# Main.net
KiCad netlist of a schematic drawn in Altium Designer
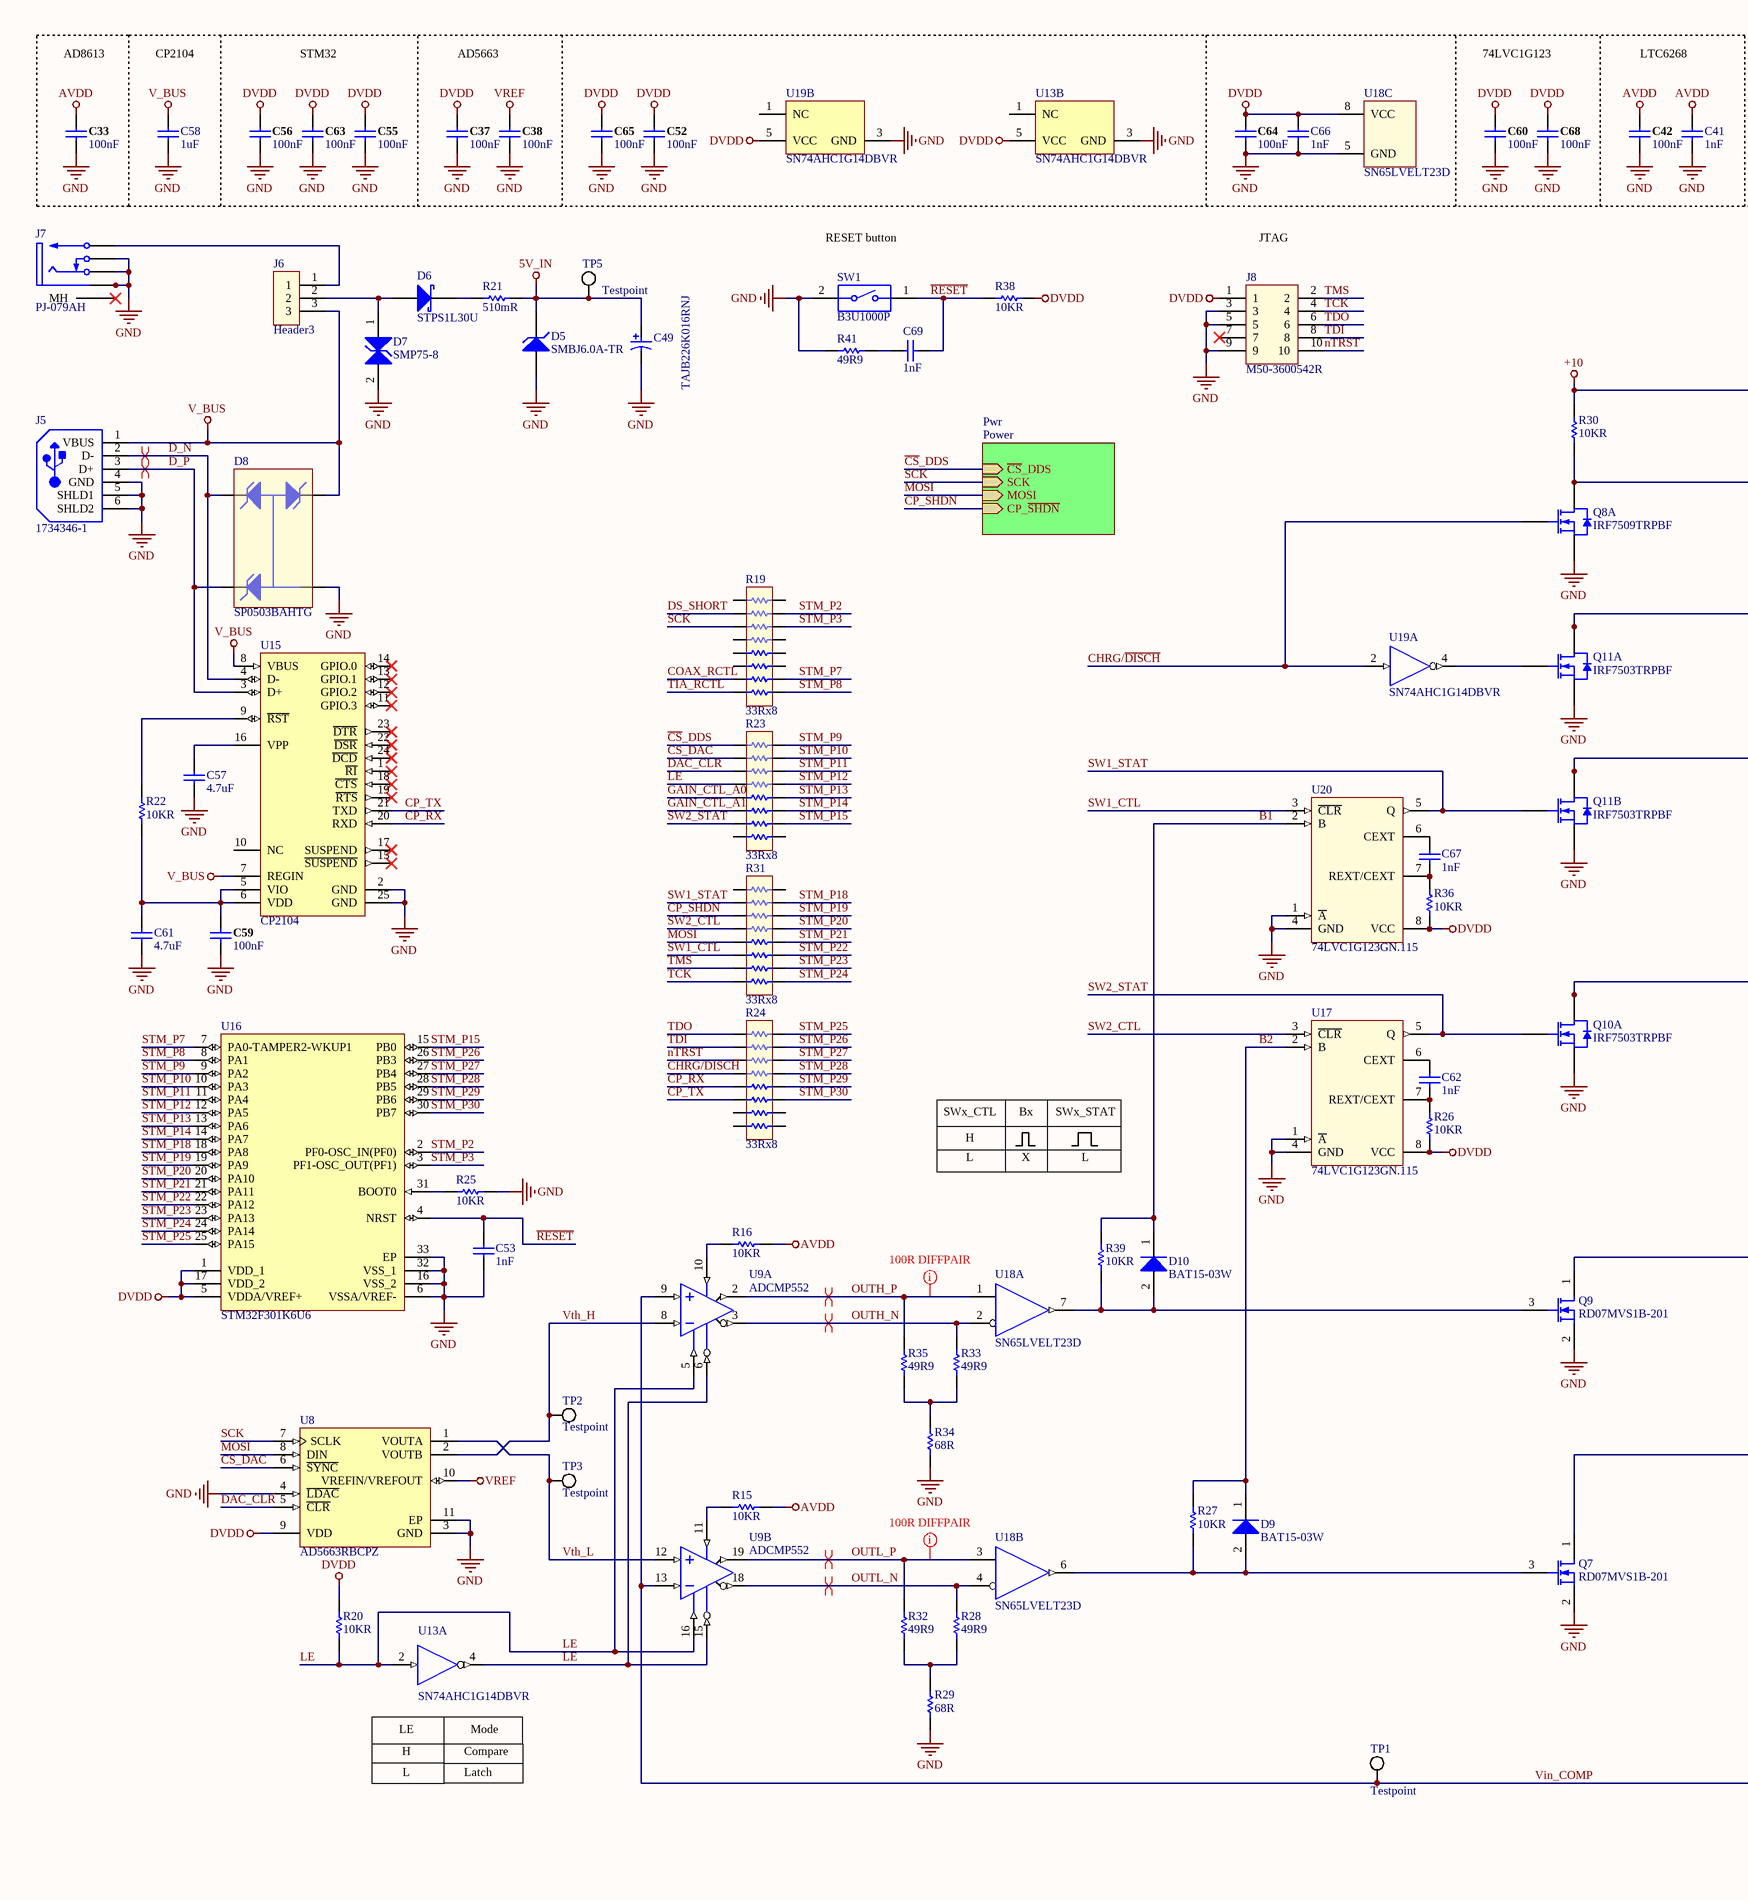
[diagram p0: Main.SchDoc, left]
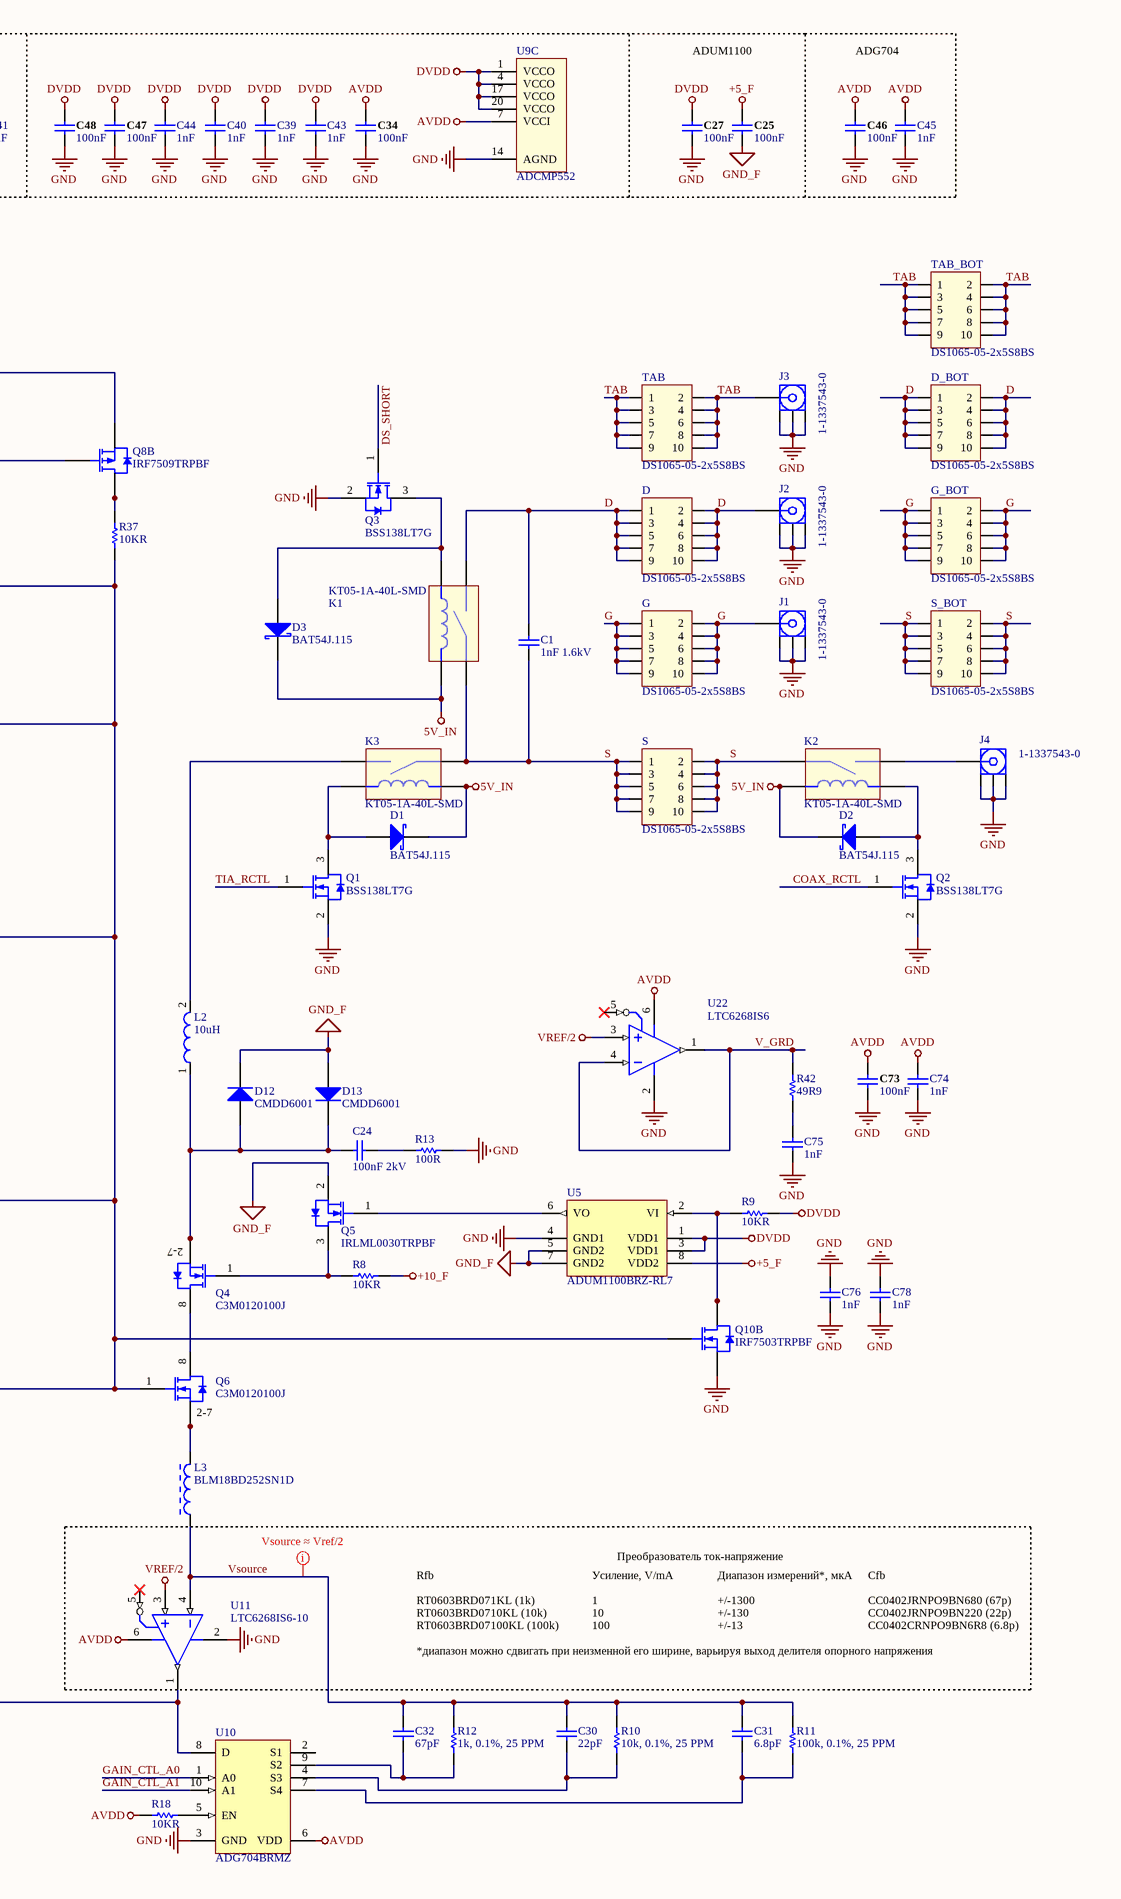
[diagram p1: Main.SchDoc, right]

(export (version "E")
  (design (tool "Eeschema 10.0.6"))
  (components
    (comp (ref "C1")
      (value "1nF 1.6kV")
      (footprint "KP1836210135")
      (description "AC and Pulse Film/Foil Capacitors\r\nRadial Potted Type")
      (libsource (lib "LocalLib") (part "KP1836210135"))
    )
    (comp (ref "C24")
      (value "100nF 2kV")
      (footprint "MKP1845D21L44")
      (description "Film Capacitors .1uF 2000volt 5%")
      (libsource (lib "LocalLib") (part "MKP1845410204"))
    )
    (comp (ref "C25")
      (value "100nF")
      (footprint "CAPC1005")
      (description "CC0402KRX7R7BB104")
      (fields (field (name "TOLERANCE") "10 %") (field (name "PUBLISHER") "Altium"))
      (libsource (lib "Altium Content Vault") (part "CAP-NP"))
    )
    (comp (ref "C27")
      (value "100nF")
      (footprint "CAPC1005")
      (description "CC0402KRX7R7BB104")
      (fields (field (name "TOLERANCE") "10 %") (field (name "PUBLISHER") "Altium"))
      (libsource (lib "Altium Content Vault") (part "CAP-NP"))
    )
    (comp (ref "C30")
      (value "22pF")
      (footprint "CAPC1005X55X25ML05T05")
      (description "CC0402JRNPO9BN220")
      (fields (field (name "TOLERANCE") "5%") (field (name "MANUFACTURER") "Yageo"))
      (libsource (lib "Altium Content Vault") (part "CAP-NP-2"))
    )
    (comp (ref "C31")
      (value "6.8pF")
      (footprint "CAPC1005X55X25ML05T05")
      (description "CC0402CRNPO9BN6R8")
      (fields (field (name "TOLERANCE") "5%") (field (name "MANUFACTURER") "Yageo"))
      (libsource (lib "Altium Content Vault") (part "CAP-NP-2"))
    )
    (comp (ref "C32")
      (value "67pF")
      (footprint "CAPC1005X55X25ML05T05")
      (description "CC0402JRNPO9BN680")
      (fields (field (name "TOLERANCE") "5%") (field (name "MANUFACTURER") "Yageo"))
      (libsource (lib "Altium Content Vault") (part "CAP-NP-2"))
    )
    (comp (ref "C33")
      (value "100nF")
      (footprint "CAPC1005")
      (description "CC0402KRX7R7BB104")
      (fields (field (name "TOLERANCE") "10 %") (field (name "PUBLISHER") "Altium"))
      (libsource (lib "Altium Content Vault") (part "CAP-NP"))
    )
    (comp (ref "C34")
      (value "100nF")
      (footprint "CAPC1005")
      (description "CC0402KRX7R7BB104")
      (fields (field (name "TOLERANCE") "10 %") (field (name "PUBLISHER") "Altium"))
      (libsource (lib "Altium Content Vault") (part "CAP-NP"))
    )
    (comp (ref "C37")
      (value "100nF")
      (footprint "CAPC1005")
      (description "CC0402KRX7R7BB104")
      (fields (field (name "TOLERANCE") "10 %") (field (name "PUBLISHER") "Altium"))
      (libsource (lib "Altium Content Vault") (part "CAP-NP"))
    )
    (comp (ref "C38")
      (value "100nF")
      (footprint "CAPC1005")
      (description "CC0402KRX7R7BB104")
      (fields (field (name "TOLERANCE") "10 %") (field (name "PUBLISHER") "Altium"))
      (libsource (lib "Altium Content Vault") (part "CAP-NP"))
    )
    (comp (ref "C39")
      (value "1nF")
      (footprint "CAPC1005X55X25ML5T10")
      (description "CC0402JRX7R9BB102")
      (fields (field (name "MANUFACTURER") "Yageo") (field (name "TOLERANCE") "10%"))
      (libsource (lib "Altium Content Vault") (part "CAP-NP-2"))
    )
    (comp (ref "C40")
      (value "1nF")
      (footprint "CAPC1005X55X25ML5T10")
      (description "CC0402JRX7R9BB102")
      (fields (field (name "MANUFACTURER") "Yageo") (field (name "TOLERANCE") "10%"))
      (libsource (lib "Altium Content Vault") (part "CAP-NP-2"))
    )
    (comp (ref "C41")
      (value "1nF")
      (footprint "CAPC1005X55X25ML5T10")
      (description "CC0402JRX7R9BB102")
      (fields (field (name "MANUFACTURER") "Yageo") (field (name "TOLERANCE") "10%"))
      (libsource (lib "Altium Content Vault") (part "CAP-NP-2"))
    )
    (comp (ref "C42")
      (value "100nF")
      (footprint "CAPC1005")
      (description "CC0402KRX7R7BB104")
      (fields (field (name "TOLERANCE") "10 %") (field (name "PUBLISHER") "Altium"))
      (libsource (lib "Altium Content Vault") (part "CAP-NP"))
    )
    (comp (ref "C43")
      (value "1nF")
      (footprint "CAPC1005X55X25ML5T10")
      (description "CC0402JRX7R9BB102")
      (fields (field (name "MANUFACTURER") "Yageo") (field (name "TOLERANCE") "10%"))
      (libsource (lib "Altium Content Vault") (part "CAP-NP-2"))
    )
    (comp (ref "C44")
      (value "1nF")
      (footprint "CAPC1005X55X25ML5T10")
      (description "CC0402JRX7R9BB102")
      (fields (field (name "MANUFACTURER") "Yageo") (field (name "TOLERANCE") "10%"))
      (libsource (lib "Altium Content Vault") (part "CAP-NP-2"))
    )
    (comp (ref "C45")
      (value "1nF")
      (footprint "CAPC1005X55X25ML5T10")
      (description "CC0402JRX7R9BB102")
      (fields (field (name "MANUFACTURER") "Yageo") (field (name "TOLERANCE") "10%"))
      (libsource (lib "Altium Content Vault") (part "CAP-NP-2"))
    )
    (comp (ref "C46")
      (value "100nF")
      (footprint "CAPC1005")
      (description "CC0402KRX7R7BB104")
      (fields (field (name "TOLERANCE") "10 %") (field (name "PUBLISHER") "Altium"))
      (libsource (lib "Altium Content Vault") (part "CAP-NP"))
    )
    (comp (ref "C47")
      (value "100nF")
      (footprint "CAPC1005")
      (description "CC0402KRX7R7BB104")
      (fields (field (name "TOLERANCE") "10 %") (field (name "PUBLISHER") "Altium"))
      (libsource (lib "Altium Content Vault") (part "CAP-NP"))
    )
    (comp (ref "C48")
      (value "100nF")
      (footprint "CAPC1005")
      (description "CC0402KRX7R7BB104")
      (fields (field (name "TOLERANCE") "10 %") (field (name "PUBLISHER") "Altium"))
      (libsource (lib "Altium Content Vault") (part "CAP-NP"))
    )
    (comp (ref "C49")
      (value "TAJB226K016RNJ")
      (footprint "AVX-TAJ-B-2_M")
      (description "Standard Tantalum, 22 uF, +/- 10%, 16 V, -55 to 125 degC, 2-Pin SMD (1210), RoHS, Tape and Reel")
      (fields (field (name "TOLERANCE") "10%") (field (name "MANUFACTURER") "AVX"))
      (libsource (lib "Altium Content Vault") (part "CAP-P-2"))
    )
    (comp (ref "C52")
      (value "100nF")
      (footprint "CAPC1005")
      (description "CC0402KRX7R7BB104")
      (fields (field (name "TOLERANCE") "10 %") (field (name "PUBLISHER") "Altium"))
      (libsource (lib "Altium Content Vault") (part "CAP-NP"))
    )
    (comp (ref "C53")
      (value "1nF")
      (footprint "CAPC1005X55X25ML5T10")
      (description "CC0402JRX7R9BB102")
      (fields (field (name "MANUFACTURER") "Yageo") (field (name "TOLERANCE") "10%"))
      (libsource (lib "Altium Content Vault") (part "CAP-NP-2"))
    )
    (comp (ref "C55")
      (value "100nF")
      (footprint "CAPC1005")
      (description "CC0402KRX7R7BB104")
      (fields (field (name "TOLERANCE") "10 %") (field (name "PUBLISHER") "Altium"))
      (libsource (lib "Altium Content Vault") (part "CAP-NP"))
    )
    (comp (ref "C56")
      (value "100nF")
      (footprint "CAPC1005")
      (description "CC0402KRX7R7BB104")
      (fields (field (name "TOLERANCE") "10 %") (field (name "PUBLISHER") "Altium"))
      (libsource (lib "Altium Content Vault") (part "CAP-NP"))
    )
    (comp (ref "C57")
      (value "4.7uF")
      (footprint "CAPC1608X90X40LL15T20")
      (description "CC0603KRX5R6BB475")
      (fields (field (name "TOLERANCE") "±10%") (field (name "MANUFACTURER") "Yageo"))
      (libsource (lib "Altium Content Vault") (part "CAP-NP-2"))
    )
    (comp (ref "C58")
      (value "1uF")
      (footprint "CAPC1608X90X40LL15T20")
      (description "CC0603KRX5R7BB105")
      (fields (field (name "TOLERANCE") "±10%") (field (name "MANUFACTURER") "Yageo"))
      (libsource (lib "Altium Content Vault") (part "CAP-NP-2"))
    )
    (comp (ref "C59")
      (value "100nF")
      (footprint "CAPC1005")
      (description "CC0402KRX7R7BB104")
      (fields (field (name "TOLERANCE") "10 %") (field (name "PUBLISHER") "Altium"))
      (libsource (lib "Altium Content Vault") (part "CAP-NP"))
    )
    (comp (ref "C60")
      (value "100nF")
      (footprint "CAPC1005")
      (description "CC0402KRX7R7BB104")
      (fields (field (name "TOLERANCE") "10 %") (field (name "PUBLISHER") "Altium"))
      (libsource (lib "Altium Content Vault") (part "CAP-NP"))
    )
    (comp (ref "C61")
      (value "4.7uF")
      (footprint "CAPC1608X90X40LL15T20")
      (description "CC0603KRX5R6BB475")
      (fields (field (name "TOLERANCE") "±10%") (field (name "MANUFACTURER") "Yageo"))
      (libsource (lib "Altium Content Vault") (part "CAP-NP-2"))
    )
    (comp (ref "C62")
      (value "1nF")
      (footprint "CAPC1005X55X25ML5T10")
      (description "CC0402JRX7R9BB102")
      (fields (field (name "MANUFACTURER") "Yageo") (field (name "TOLERANCE") "10%"))
      (libsource (lib "Altium Content Vault") (part "CAP-NP-2"))
    )
    (comp (ref "C63")
      (value "100nF")
      (footprint "CAPC1005")
      (description "CC0402KRX7R7BB104")
      (fields (field (name "TOLERANCE") "10 %") (field (name "PUBLISHER") "Altium"))
      (libsource (lib "Altium Content Vault") (part "CAP-NP"))
    )
    (comp (ref "C64")
      (value "100nF")
      (footprint "CAPC1005")
      (description "CC0402KRX7R7BB104")
      (fields (field (name "TOLERANCE") "10 %") (field (name "PUBLISHER") "Altium"))
      (libsource (lib "Altium Content Vault") (part "CAP-NP"))
    )
    (comp (ref "C65")
      (value "100nF")
      (footprint "CAPC1005")
      (description "CC0402KRX7R7BB104")
      (fields (field (name "TOLERANCE") "10 %") (field (name "PUBLISHER") "Altium"))
      (libsource (lib "Altium Content Vault") (part "CAP-NP"))
    )
    (comp (ref "C66")
      (value "1nF")
      (footprint "CAPC1005X55X25ML5T10")
      (description "CC0402JRX7R9BB102")
      (fields (field (name "MANUFACTURER") "Yageo") (field (name "TOLERANCE") "10%"))
      (libsource (lib "Altium Content Vault") (part "CAP-NP-2"))
    )
    (comp (ref "C67")
      (value "1nF")
      (footprint "CAPC1005X55X25ML5T10")
      (description "CC0402JRX7R9BB102")
      (fields (field (name "MANUFACTURER") "Yageo") (field (name "TOLERANCE") "10%"))
      (libsource (lib "Altium Content Vault") (part "CAP-NP-2"))
    )
    (comp (ref "C68")
      (value "100nF")
      (footprint "CAPC1005")
      (description "CC0402KRX7R7BB104")
      (fields (field (name "TOLERANCE") "10 %") (field (name "PUBLISHER") "Altium"))
      (libsource (lib "Altium Content Vault") (part "CAP-NP"))
    )
    (comp (ref "C69")
      (value "1nF")
      (footprint "CAPC1005X55X25ML5T10")
      (description "CC0402JRX7R9BB102")
      (fields (field (name "MANUFACTURER") "Yageo") (field (name "TOLERANCE") "10%"))
      (libsource (lib "Altium Content Vault") (part "CAP-NP-2"))
    )
    (comp (ref "C73")
      (value "100nF")
      (footprint "CAPC1005")
      (description "CC0402KRX7R7BB104")
      (fields (field (name "TOLERANCE") "10 %") (field (name "PUBLISHER") "Altium"))
      (libsource (lib "Altium Content Vault") (part "CAP-NP"))
    )
    (comp (ref "C74")
      (value "1nF")
      (footprint "CAPC1005X55X25ML5T10")
      (description "CC0402JRX7R9BB102")
      (fields (field (name "MANUFACTURER") "Yageo") (field (name "TOLERANCE") "10%"))
      (libsource (lib "Altium Content Vault") (part "CAP-NP-2"))
    )
    (comp (ref "C75")
      (value "1nF")
      (footprint "CAPC1005X55X25ML5T10")
      (description "CC0402JRX7R9BB102")
      (fields (field (name "MANUFACTURER") "Yageo") (field (name "TOLERANCE") "10%"))
      (libsource (lib "Altium Content Vault") (part "CAP-NP-2"))
    )
    (comp (ref "C76")
      (value "1nF")
      (footprint "CAPC1005X55X25ML5T10")
      (description "CC0402JRX7R9BB102")
      (fields (field (name "MANUFACTURER") "Yageo") (field (name "TOLERANCE") "10%"))
      (libsource (lib "Altium Content Vault") (part "CAP-NP-2"))
    )
    (comp (ref "C78")
      (value "1nF")
      (footprint "CAPC1005X55X25ML5T10")
      (description "CC0402JRX7R9BB102")
      (fields (field (name "MANUFACTURER") "Yageo") (field (name "TOLERANCE") "10%"))
      (libsource (lib "Altium Content Vault") (part "CAP-NP-2"))
    )
    (comp (ref "D")
      (value "DS1065-05-2x5S8BS")
      (footprint "DS1065-05-2x5S8BS")
      (libsource (lib "LocalLib") (part "DS1065-05-2x5S8BS"))
    )
    (comp (ref "D1")
      (value "BAT54J.115")
      (footprint "SOD-323")
      (libsource (lib "LocalLib") (part "BAT54J.115"))
    )
    (comp (ref "D2")
      (value "BAT54J.115")
      (footprint "SOD-323")
      (libsource (lib "LocalLib") (part "BAT54J.115"))
    )
    (comp (ref "D3")
      (value "BAT54J.115")
      (footprint "SOD-323")
      (libsource (lib "LocalLib") (part "BAT54J.115"))
    )
    (comp (ref "D5")
      (value "SMBJ6.0A-TR")
      (footprint "DO-214AA")
      (libsource (lib "LocalLib") (part "SMBJ6.0A-TR"))
    )
    (comp (ref "D6")
      (value "STPS1L30U")
      (footprint "DO-214AA")
      (libsource (lib "LocalLib") (part "STPS1L30U"))
    )
    (comp (ref "D7")
      (value "SMP75-8")
      (footprint "DO-214AA")
      (description "Trisil™ for telecom equipment protection")
      (libsource (lib "LocalLib") (part "SMP75-8"))
    )
    (comp (ref "D8")
      (value "SP0503BAHTG")
      (footprint "SOT143-4")
      (description "30pF 30kV Unidirectional TVS Array")
      (libsource (lib "Diodes") (part "SP0503BAHTG"))
    )
    (comp (ref "D9")
      (value "BAT15-03W")
      (footprint "SOD-323")
      (description "BAT1503WE6327HTSA1")
      (libsource (lib "LocalLib") (part "INF-BAT15-03W-2"))
    )
    (comp (ref "D10")
      (value "BAT15-03W")
      (footprint "SOD-323")
      (description "BAT1503WE6327HTSA1")
      (libsource (lib "LocalLib") (part "INF-BAT15-03W-2"))
    )
    (comp (ref "D12")
      (value "CMDD6001")
      (footprint "SOD-323")
      (description "TVS")
      (libsource (lib "LocalLib") (part "CMDD6001"))
    )
    (comp (ref "D13")
      (value "CMDD6001")
      (footprint "SOD-323")
      (description "TVS")
      (libsource (lib "LocalLib") (part "CMDD6001"))
    )
    (comp (ref "D_BOT")
      (value "DS1065-05-2x5S8BS")
      (footprint "DS1065-05-2x5S8BS")
      (libsource (lib "LocalLib") (part "DS1065-05-2x5S8BS"))
    )
    (comp (ref "G")
      (value "DS1065-05-2x5S8BS")
      (footprint "DS1065-05-2x5S8BS")
      (libsource (lib "LocalLib") (part "DS1065-05-2x5S8BS"))
    )
    (comp (ref "G_BOT")
      (value "DS1065-05-2x5S8BS")
      (footprint "DS1065-05-2x5S8BS")
      (libsource (lib "LocalLib") (part "DS1065-05-2x5S8BS"))
    )
    (comp (ref "J1")
      (value "1-1337543-0")
      (footprint "1-1337543-0")
      (libsource (lib "LocalLib") (part "1-1337543-0"))
    )
    (comp (ref "J2")
      (value "1-1337543-0")
      (footprint "1-1337543-0")
      (libsource (lib "LocalLib") (part "1-1337543-0"))
    )
    (comp (ref "J3")
      (value "1-1337543-0")
      (footprint "1-1337543-0")
      (libsource (lib "LocalLib") (part "1-1337543-0"))
    )
    (comp (ref "J4")
      (value "1-1337543-0")
      (footprint "1-1337543-0")
      (libsource (lib "LocalLib") (part "1-1337543-0"))
    )
    (comp (ref "J5")
      (value "1734346-1")
      (footprint "TECO-1734346-1_V")
      (description "USB-B Receptacle Connector, Height 10.87 mm, 0 to 50 degC, RoHS, Tray")
      (fields (field (name "MANUFACTURER") "TE Connectivity"))
      (libsource (lib "Altium Content Vault") (part "USB-4-2SHLD"))
    )
    (comp (ref "J6") (value "Header3") (footprint "Header3") (libsource (lib "LocalLib") (part "Header3")))
    (comp (ref "J7")
      (value "PJ-079AH")
      (footprint "PJ-079AH")
      (description "DC POWER JACK")
      (libsource (lib "LocalLib") (part "PJ-079AH"))
    )
    (comp (ref "J8")
      (value "M50-3600542R")
      (footprint "M50-3600542R")
      (libsource (lib "LocalLib") (part "M50-3600542R"))
    )
    (comp (ref "K1")
      (value "KT05-1A-40L-SMD")
      (footprint "KT05-1A-40L-SMD")
      (libsource (lib "") (part "KT05-1A-40L-SMD_1"))
    )
    (comp (ref "K2")
      (value "KT05-1A-40L-SMD")
      (footprint "KT05-1A-40L-SMD")
      (libsource (lib "") (part "KT05-1A-40L-SMD_2"))
    )
    (comp (ref "K3")
      (value "KT05-1A-40L-SMD")
      (footprint "KT05-1A-40L-SMD")
      (libsource (lib "LocalLib") (part "KT05-1A-40L-SMD"))
    )
    (comp (ref "L2")
      (value "10uH")
      (footprint "L1210H1.2")
      (description "1277AS-H-100M=P2")
      (libsource (lib "LocalLib") (part "1277AS-H-100M=P2"))
    )
    (comp (ref "L3")
      (value "BLM18BD252SN1D")
      (footprint "MURA-BLM18-F-H1-CHIP-2_V")
      (fields (field (name "MANUFACTURER") "Murata"))
      (libsource (lib "Altium Content Vault") (part "MURA-FB-2"))
    )
    (comp (ref "Q1")
      (value "BSS138LT7G")
      (footprint "SOT-23-3")
      (description "Power MOSFET\r\n200 mA, 50 V")
      (libsource (lib "LocalLib") (part "BSS138LT7G"))
    )
    (comp (ref "Q2")
      (value "BSS138LT7G")
      (footprint "SOT-23-3")
      (description "Power MOSFET\r\n200 mA, 50 V")
      (libsource (lib "LocalLib") (part "BSS138LT7G"))
    )
    (comp (ref "Q3")
      (value "BSS138LT7G")
      (footprint "SOT-23-3")
      (description "Power MOSFET\r\n200 mA, 50 V")
      (libsource (lib "LocalLib") (part "BSS138LT7G"))
    )
    (comp (ref "Q4")
      (value "C3M0120100J")
      (footprint "D2PAK-7L")
      (description "Silicon Carbide Power MOSFET")
      (libsource (lib "LocalLib") (part "C3M0120100J"))
    )
    (comp (ref "Q5")
      (value "IRLML0030TRPBF")
      (footprint "INTR-SOT-23-3_V")
      (description "HEXFET(R) Power MOSFET, 1.3 W, 4.4 ns, -55 to 150 degC, 3-Pin SOT-23, RoHS, Tape and Reel")
      (fields (field (name "MANUFACTURER") "International Rectifier"))
      (libsource (lib "Altium Content Vault") (part "NEMOS-GSD-3"))
    )
    (comp (ref "Q6")
      (value "C3M0120100J")
      (footprint "D2PAK-7L")
      (description "Silicon Carbide Power MOSFET")
      (libsource (lib "LocalLib") (part "C3M0120100J"))
    )
    (comp (ref "Q7")
      (value "RD07MVS1B-201")
      (footprint "RD07MVS1B")
      (description "RoHS Compliant product, Silicon MOSFET Power Transistor,175MHz,520MHz,7W")
      (libsource (lib "LocalLib") (part "RD07MVS1B-201"))
    )
    (comp (ref "Q8")
      (value "IRF7509TRPBF")
      (footprint "Micro8")
      (libsource (lib "LocalLib") (part "IRF7509TRPBF"))
    )
    (comp (ref "Q9")
      (value "RD07MVS1B-201")
      (footprint "RD07MVS1B")
      (description "RoHS Compliant product, Silicon MOSFET Power Transistor,175MHz,520MHz,7W")
      (libsource (lib "LocalLib") (part "RD07MVS1B-201"))
    )
    (comp (ref "Q10")
      (value "IRF7503TRPBF")
      (footprint "Micro8")
      (libsource (lib "LocalLib") (part "IRF7503TRPBF"))
    )
    (comp (ref "Q11")
      (value "IRF7503TRPBF")
      (footprint "Micro8")
      (libsource (lib "LocalLib") (part "IRF7503TRPBF"))
    )
    (comp (ref "R8")
      (value "10KR")
      (footprint "RESC1005X40X25LL05T10")
      (description "RC0402FR-0710KL")
      (fields (field (name "MANUFACTURER") "Yageo / Phycomp"))
      (libsource (lib "Altium Content Vault") (part "RES"))
    )
    (comp (ref "R9")
      (value "10KR")
      (footprint "RESC1005X40X25LL05T10")
      (description "RC0402FR-0710KL")
      (fields (field (name "MANUFACTURER") "Yageo / Phycomp"))
      (libsource (lib "Altium Content Vault") (part "RES"))
    )
    (comp (ref "R10")
      (value "10k, 0.1%, 25 PPM")
      (footprint "RT0603")
      (description "RT0603BRD0710KL")
      (libsource (lib "LocalLib") (part "RT0603BRD0710KL"))
    )
    (comp (ref "R11")
      (value "100k, 0.1%, 25 PPM")
      (footprint "RT0603")
      (description "RT0603BRD07100KL")
      (libsource (lib "LocalLib") (part "RT0603BRD07100KL"))
    )
    (comp (ref "R12")
      (value "1k, 0.1%, 25 PPM")
      (footprint "RT0603")
      (description "RT0603BRD071KL")
      (libsource (lib "LocalLib") (part "RT0603BRD071KL"))
    )
    (comp (ref "R13") (value "100R") (footprint "OF101JE") (libsource (lib "LocalLib") (part "OF101JE")))
    (comp (ref "R15")
      (value "10KR")
      (footprint "RESC1005X40X25LL05T10")
      (description "RC0402FR-0710KL")
      (fields (field (name "MANUFACTURER") "Yageo / Phycomp"))
      (libsource (lib "Altium Content Vault") (part "RES"))
    )
    (comp (ref "R16")
      (value "10KR")
      (footprint "RESC1005X40X25LL05T10")
      (description "RC0402FR-0710KL")
      (fields (field (name "MANUFACTURER") "Yageo / Phycomp"))
      (libsource (lib "Altium Content Vault") (part "RES"))
    )
    (comp (ref "R18")
      (value "10KR")
      (footprint "RESC1005X40X25LL05T10")
      (description "RC0402FR-0710KL")
      (fields (field (name "MANUFACTURER") "Yageo / Phycomp"))
      (libsource (lib "Altium Content Vault") (part "RES"))
    )
    (comp (ref "R19")
      (value "33Rx8")
      (footprint "R0402H60x4")
      (description "EXB-2HV330JV")
      (libsource (lib "Resistors") (part "EXB-2HV330JV"))
    )
    (comp (ref "R20")
      (value "10KR")
      (footprint "RESC1005X40X25LL05T10")
      (description "RC0402FR-0710KL")
      (fields (field (name "MANUFACTURER") "Yageo / Phycomp"))
      (libsource (lib "Altium Content Vault") (part "RES"))
    )
    (comp (ref "R21")
      (value "510mR")
      (footprint "RESC3116X65X40NL10T20")
      (description "RL1206FR-070R51L")
      (fields (field (name "MANUFACTURER") "Yageo") (field (name "PART NUMBER") "RL1206FR-070R068L"))
      (libsource (lib "Altium Content Vault") (part "RES"))
    )
    (comp (ref "R22")
      (value "10KR")
      (footprint "RESC1005X40X25LL05T10")
      (description "RC0402FR-0710KL")
      (fields (field (name "MANUFACTURER") "Yageo / Phycomp"))
      (libsource (lib "Altium Content Vault") (part "RES"))
    )
    (comp (ref "R23")
      (value "33Rx8")
      (footprint "R0402H60x4")
      (description "EXB-2HV330JV")
      (libsource (lib "Resistors") (part "EXB-2HV330JV"))
    )
    (comp (ref "R24")
      (value "33Rx8")
      (footprint "R0402H60x4")
      (description "EXB-2HV330JV")
      (libsource (lib "Resistors") (part "EXB-2HV330JV"))
    )
    (comp (ref "R25")
      (value "10KR")
      (footprint "RESC1005X40X25LL05T10")
      (description "RC0402FR-0710KL")
      (fields (field (name "MANUFACTURER") "Yageo / Phycomp"))
      (libsource (lib "Altium Content Vault") (part "RES"))
    )
    (comp (ref "R26")
      (value "10KR")
      (footprint "RESC1005X40X25LL05T10")
      (description "RC0402FR-0710KL")
      (fields (field (name "MANUFACTURER") "Yageo / Phycomp"))
      (libsource (lib "Altium Content Vault") (part "RES"))
    )
    (comp (ref "R27")
      (value "10KR")
      (footprint "RESC1005X40X25LL05T10")
      (description "RC0402FR-0710KL")
      (fields (field (name "MANUFACTURER") "Yageo / Phycomp"))
      (libsource (lib "Altium Content Vault") (part "RES"))
    )
    (comp (ref "R28")
      (value "49R9")
      (footprint "RESC1005X40X25LL05T10")
      (description "RC0402FR-0749R9L")
      (fields (field (name "MANUFACTURER") "Yageo / Phycomp"))
      (libsource (lib "Altium Content Vault") (part "RES"))
    )
    (comp (ref "R29")
      (value "68R")
      (footprint "RESC1005X40X25ML05T10")
      (description "RC0402FR-0768RL")
      (fields (field (name "MANUFACTURER") "Yageo / Phycomp"))
      (libsource (lib "Altium Content Vault") (part "RES"))
    )
    (comp (ref "R30")
      (value "10KR")
      (footprint "RESC1005X40X25LL05T10")
      (description "RC0402FR-0710KL")
      (fields (field (name "MANUFACTURER") "Yageo / Phycomp"))
      (libsource (lib "Altium Content Vault") (part "RES"))
    )
    (comp (ref "R31")
      (value "33Rx8")
      (footprint "R0402H60x4")
      (description "EXB-2HV330JV")
      (libsource (lib "Resistors") (part "EXB-2HV330JV"))
    )
    (comp (ref "R32")
      (value "49R9")
      (footprint "RESC1005X40X25LL05T10")
      (description "RC0402FR-0749R9L")
      (fields (field (name "MANUFACTURER") "Yageo / Phycomp"))
      (libsource (lib "Altium Content Vault") (part "RES"))
    )
    (comp (ref "R33")
      (value "49R9")
      (footprint "RESC1005X40X25LL05T10")
      (description "RC0402FR-0749R9L")
      (fields (field (name "MANUFACTURER") "Yageo / Phycomp"))
      (libsource (lib "Altium Content Vault") (part "RES"))
    )
    (comp (ref "R34")
      (value "68R")
      (footprint "RESC1005X40X25ML05T10")
      (description "RC0402FR-0768RL")
      (fields (field (name "MANUFACTURER") "Yageo / Phycomp"))
      (libsource (lib "Altium Content Vault") (part "RES"))
    )
    (comp (ref "R35")
      (value "49R9")
      (footprint "RESC1005X40X25LL05T10")
      (description "RC0402FR-0749R9L")
      (fields (field (name "MANUFACTURER") "Yageo / Phycomp"))
      (libsource (lib "Altium Content Vault") (part "RES"))
    )
    (comp (ref "R36")
      (value "10KR")
      (footprint "RESC1005X40X25LL05T10")
      (description "RC0402FR-0710KL")
      (fields (field (name "MANUFACTURER") "Yageo / Phycomp"))
      (libsource (lib "Altium Content Vault") (part "RES"))
    )
    (comp (ref "R37")
      (value "10KR")
      (footprint "RESC1005X40X25LL05T10")
      (description "RC0402FR-0710KL")
      (fields (field (name "MANUFACTURER") "Yageo / Phycomp"))
      (libsource (lib "Altium Content Vault") (part "RES"))
    )
    (comp (ref "R38")
      (value "10KR")
      (footprint "RESC1005X40X25LL05T10")
      (description "RC0402FR-0710KL")
      (fields (field (name "MANUFACTURER") "Yageo / Phycomp"))
      (libsource (lib "Altium Content Vault") (part "RES"))
    )
    (comp (ref "R39")
      (value "10KR")
      (footprint "RESC1005X40X25LL05T10")
      (description "RC0402FR-0710KL")
      (fields (field (name "MANUFACTURER") "Yageo / Phycomp"))
      (libsource (lib "Altium Content Vault") (part "RES"))
    )
    (comp (ref "R41")
      (value "49R9")
      (footprint "RESC1005X40X25LL05T10")
      (description "RC0402FR-0749R9L")
      (fields (field (name "MANUFACTURER") "Yageo / Phycomp"))
      (libsource (lib "Altium Content Vault") (part "RES"))
    )
    (comp (ref "R42")
      (value "49R9")
      (footprint "RESC1005X40X25LL05T10")
      (description "RC0402FR-0749R9L")
      (fields (field (name "MANUFACTURER") "Yageo / Phycomp"))
      (libsource (lib "Altium Content Vault") (part "RES"))
    )
    (comp (ref "S")
      (value "DS1065-05-2x5S8BS")
      (footprint "DS1065-05-2x5S8BS")
      (libsource (lib "LocalLib") (part "DS1065-05-2x5S8BS"))
    )
    (comp (ref "SW1")
      (value "B3U1000P")
      (footprint "B3U")
      (description "Ultra-small Surface-mounting Tactile\r\nSwitches with High Contact Reliability")
      (libsource (lib "Buttons") (part "B3U1000P"))
    )
    (comp (ref "S_BOT")
      (value "DS1065-05-2x5S8BS")
      (footprint "DS1065-05-2x5S8BS")
      (libsource (lib "LocalLib") (part "DS1065-05-2x5S8BS"))
    )
    (comp (ref "TAB")
      (value "DS1065-05-2x5S8BS")
      (footprint "DS1065-05-2x5S8BS")
      (libsource (lib "LocalLib") (part "DS1065-05-2x5S8BS"))
    )
    (comp (ref "TAB_BOT")
      (value "DS1065-05-2x5S8BS")
      (footprint "DS1065-05-2x5S8BS")
      (libsource (lib "LocalLib") (part "DS1065-05-2x5S8BS"))
    )
    (comp (ref "TP1")
      (value "Testpoint")
      (footprint "TESTPOINT")
      (libsource (lib "LocalLib") (part "Testpoint"))
    )
    (comp (ref "TP2")
      (value "Testpoint")
      (footprint "TESTPOINT")
      (libsource (lib "LocalLib") (part "Testpoint"))
    )
    (comp (ref "TP3")
      (value "Testpoint")
      (footprint "TESTPOINT")
      (libsource (lib "LocalLib") (part "Testpoint"))
    )
    (comp (ref "TP5")
      (value "Testpoint")
      (footprint "TESTPOINT")
      (libsource (lib "LocalLib") (part "Testpoint"))
    )
    (comp (ref "U5")
      (value "ADUM1100BRZ-RL7")
      (footprint "ADI-R-8_M")
      (fields (field (name "MANUFACTURER") "Analog Devices"))
      (libsource (lib "Altium Content Vault") (part "ADI-ADUMX100-R-8"))
    )
    (comp (ref "U8")
      (value "AD5663RBCPZ")
      (footprint "LFCSP-10")
      (description "Dual 12-/14-/16-Bit nanoDAC with\r\n5 ppm/°C On-Chip Reference")
      (libsource (lib "LocalLib") (part "AD5663RBCPZ"))
    )
    (comp (ref "U9")
      (value "ADCMP552")
      (footprint "QSOP-20")
      (description "Single-Supply, High Speed\r\nPECL/LVPECL Comparator")
      (libsource (lib "LocalLib") (part "ADCMP552"))
    )
    (comp (ref "U10")
      (value "ADG704BRMZ")
      (footprint "ADI-RM-10_M")
      (description "CMOS Low Voltage 4 Ohm, 4-Channel Multiplexer, -40 to 85 degC, 10-pin SOP (RM-10), Tube")
      (fields (field (name "MANUFACTURER") "Analog Devices"))
      (libsource (lib "Altium Content Vault") (part "ADI-ADG704-RM-10"))
    )
    (comp (ref "U11")
      (value "LTC6268IS6-10")
      (footprint "SOT-23-6")
      (description "4GHz Ultra-Low Bias\r\nCurrent FET Input Op Amp")
      (libsource (lib "LocalLib") (part "LTC6268IS6-10"))
    )
    (comp (ref "U13")
      (value "SN74AHC1G14DBVR")
      (footprint "DBV0005A_L")
      (fields (field (name "MANUFACTURER") "Texas Instruments"))
      (libsource (lib "Altium Content Vault") (part "TI-SN74XXX1XX4-XX-5"))
    )
    (comp (ref "U15") (value "CP2104") (footprint "QFN-24") (libsource (lib "LocalLib") (part "CP2104")))
    (comp (ref "U16")
      (value "STM32F301K6U6")
      (footprint "STM-UFQFPN32_L")
      (libsource (lib "Altium Content Vault") (part "MC-ARM-STM32F301-UFQFPN32"))
    )
    (comp (ref "U17")
      (value "74LVC1G123GN.115")
      (footprint "SOT1116")
      (description "Single retriggerable monostable multivibrator")
      (libsource (lib "LocalLib") (part "74LVC1G123GN.115"))
    )
    (comp (ref "U18")
      (value "SN65LVELT23D")
      (footprint "SOIC-8")
      (description "3.3-V Dual Differential LVPECL/LVDS Buffer to LVTTL Translator")
      (libsource (lib "LocalLib") (part "SN65LVELT23D"))
    )
    (comp (ref "U19")
      (value "SN74AHC1G14DBVR")
      (footprint "DBV0005A_L")
      (fields (field (name "MANUFACTURER") "Texas Instruments"))
      (libsource (lib "Altium Content Vault") (part "TI-SN74XXX1XX4-XX-5"))
    )
    (comp (ref "U20")
      (value "74LVC1G123GN.115")
      (footprint "SOT1116")
      (description "Single retriggerable monostable multivibrator")
      (libsource (lib "LocalLib") (part "74LVC1G123GN.115"))
    )
    (comp (ref "U22")
      (value "LTC6268IS6")
      (footprint "SOT-23-6")
      (description "500MHz Ultra-Low Bias\r\nCurrent FET Input Op Amp")
      (libsource (lib "LocalLib") (part "LTC6268IS6"))
    )
  )
  (nets
    (net (code "1") (name "+5_F") (class "Default")
      (node (ref "C25") (pin "1") (pinfunction "1_1") (pintype "passive"))
      (node (ref "U5") (pin "8") (pinfunction "VDD2_8") (pintype "power_in"))
    )
    (net (code "2") (name "+10") (class "Default")
      (node (ref "Q8") (pin "3") (pinfunction "3_3") (pintype "passive"))
      (node (ref "R30") (pin "1") (pinfunction "1_1") (pintype "passive"))
    )
    (net (code "3") (name "+10_F") (class "Default")
      (node (ref "R8") (pin "2") (pinfunction "2_2") (pintype "passive"))
    )
    (net (code "4") (name "/B1") (class "Default")
      (node (ref "D10") (pin "1") (pinfunction "K_1") (pintype "passive"))
      (node (ref "R39") (pin "1") (pinfunction "1_1") (pintype "passive"))
      (node (ref "U20") (pin "2") (pinfunction "B_2") (pintype "input"))
    )
    (net (code "5") (name "/B2") (class "Default")
      (node (ref "D9") (pin "1") (pinfunction "K_1") (pintype "passive"))
      (node (ref "R27") (pin "1") (pinfunction "1_1") (pintype "passive"))
      (node (ref "U17") (pin "2") (pinfunction "B_2") (pintype "input"))
    )
    (net (code "6") (name "/CHRG{slash}~{DISCH}") (class "Default")
      (node (ref "Q8") (pin "2") (pinfunction "2_2") (pintype "passive"))
      (node (ref "R24") (pin "4") (pinfunction "4_4") (pintype "passive"))
      (node (ref "U19") (pin "2") (pinfunction "A_2") (pintype "input"))
    )
    (net (code "7") (name "/COAX_RCTL") (class "Default")
      (node (ref "Q2") (pin "1") (pinfunction "G_1") (pintype "passive"))
      (node (ref "R19") (pin "7") (pinfunction "7_7") (pintype "passive"))
    )
    (net (code "8") (name "/CP_RX") (class "Default")
      (node (ref "R24") (pin "5") (pinfunction "5_5") (pintype "passive"))
      (node (ref "U15") (pin "20") (pinfunction "RXD_20") (pintype "input"))
    )
    (net (code "9") (name "/CP_TX") (class "Default")
      (node (ref "R24") (pin "6") (pinfunction "6_6") (pintype "passive"))
      (node (ref "U15") (pin "21") (pinfunction "TXD_21") (pintype "output"))
    )
    (net (code "10") (name "/CP_~{SHDN}") (class "Default")
      (node (ref "R31") (pin "3") (pinfunction "3_3") (pintype "passive"))
    )
    (net (code "11") (name "/D") (class "Default")
      (node (ref "C1") (pin "2") (pinfunction "2_2") (pintype "passive"))
      (node (ref "D") (pin "1") (pinfunction "1_1") (pintype "passive"))
      (node (ref "D") (pin "10") (pinfunction "10_10") (pintype "passive"))
      (node (ref "D") (pin "2") (pinfunction "2_2") (pintype "passive"))
      (node (ref "D") (pin "3") (pinfunction "3_3") (pintype "passive"))
      (node (ref "D") (pin "4") (pinfunction "4_4") (pintype "passive"))
      (node (ref "D") (pin "5") (pinfunction "5_5") (pintype "passive"))
      (node (ref "D") (pin "6") (pinfunction "6_6") (pintype "passive"))
      (node (ref "D") (pin "7") (pinfunction "7_7") (pintype "passive"))
      (node (ref "D") (pin "8") (pinfunction "8_8") (pintype "passive"))
      (node (ref "D") (pin "9") (pinfunction "9_9") (pintype "passive"))
      (node (ref "D_BOT") (pin "1") (pinfunction "1_1") (pintype "passive"))
      (node (ref "D_BOT") (pin "10") (pinfunction "10_10") (pintype "passive"))
      (node (ref "D_BOT") (pin "2") (pinfunction "2_2") (pintype "passive"))
      (node (ref "D_BOT") (pin "3") (pinfunction "3_3") (pintype "passive"))
      (node (ref "D_BOT") (pin "4") (pinfunction "4_4") (pintype "passive"))
      (node (ref "D_BOT") (pin "5") (pinfunction "5_5") (pintype "passive"))
      (node (ref "D_BOT") (pin "6") (pinfunction "6_6") (pintype "passive"))
      (node (ref "D_BOT") (pin "7") (pinfunction "7_7") (pintype "passive"))
      (node (ref "D_BOT") (pin "8") (pinfunction "8_8") (pintype "passive"))
      (node (ref "D_BOT") (pin "9") (pinfunction "9_9") (pintype "passive"))
      (node (ref "J2") (pin "1") (pinfunction "1_1") (pintype "passive"))
      (node (ref "K1") (pin "2") (pinfunction "2_2") (pintype "passive"))
    )
    (net (code "12") (name "/DAC_~{CLR}") (class "Default")
      (node (ref "R23") (pin "3") (pinfunction "3_3") (pintype "passive"))
      (node (ref "U8") (pin "5") (pinfunction "~{CLR}_5") (pintype "input"))
    )
    (net (code "13") (name "/DS_SHORT") (class "Default")
      (node (ref "Q3") (pin "1") (pinfunction "G_1") (pintype "passive"))
      (node (ref "R19") (pin "2") (pinfunction "2_2") (pintype "passive"))
    )
    (net (code "14") (name "/D_N") (class "Default")
      (node (ref "D8") (pin "3") (pinfunction "3_3") (pintype "passive"))
      (node (ref "J5") (pin "2") (pinfunction "D-_2") (pintype "passive"))
      (node (ref "U15") (pin "4") (pinfunction "D-_4") (pintype "bidirectional"))
    )
    (net (code "15") (name "/D_P") (class "Default")
      (node (ref "D8") (pin "4") (pinfunction "4_4") (pintype "passive"))
      (node (ref "J5") (pin "3") (pinfunction "D+_3") (pintype "passive"))
      (node (ref "U15") (pin "3") (pinfunction "D+_3") (pintype "bidirectional"))
    )
    (net (code "16") (name "/G") (class "Default")
      (node (ref "G") (pin "1") (pinfunction "1_1") (pintype "passive"))
      (node (ref "G") (pin "10") (pinfunction "10_10") (pintype "passive"))
      (node (ref "G") (pin "2") (pinfunction "2_2") (pintype "passive"))
      (node (ref "G") (pin "3") (pinfunction "3_3") (pintype "passive"))
      (node (ref "G") (pin "4") (pinfunction "4_4") (pintype "passive"))
      (node (ref "G") (pin "5") (pinfunction "5_5") (pintype "passive"))
      (node (ref "G") (pin "6") (pinfunction "6_6") (pintype "passive"))
      (node (ref "G") (pin "7") (pinfunction "7_7") (pintype "passive"))
      (node (ref "G") (pin "8") (pinfunction "8_8") (pintype "passive"))
      (node (ref "G") (pin "9") (pinfunction "9_9") (pintype "passive"))
      (node (ref "G_BOT") (pin "1") (pinfunction "1_1") (pintype "passive"))
      (node (ref "G_BOT") (pin "10") (pinfunction "10_10") (pintype "passive"))
      (node (ref "G_BOT") (pin "2") (pinfunction "2_2") (pintype "passive"))
      (node (ref "G_BOT") (pin "3") (pinfunction "3_3") (pintype "passive"))
      (node (ref "G_BOT") (pin "4") (pinfunction "4_4") (pintype "passive"))
      (node (ref "G_BOT") (pin "5") (pinfunction "5_5") (pintype "passive"))
      (node (ref "G_BOT") (pin "6") (pinfunction "6_6") (pintype "passive"))
      (node (ref "G_BOT") (pin "7") (pinfunction "7_7") (pintype "passive"))
      (node (ref "G_BOT") (pin "8") (pinfunction "8_8") (pintype "passive"))
      (node (ref "G_BOT") (pin "9") (pinfunction "9_9") (pintype "passive"))
      (node (ref "J1") (pin "1") (pinfunction "1_1") (pintype "passive"))
    )
    (net (code "17") (name "/GAIN_CTL_A0") (class "Default")
      (node (ref "R23") (pin "5") (pinfunction "5_5") (pintype "passive"))
      (node (ref "U10") (pin "1") (pinfunction "A0_1") (pintype "input"))
    )
    (net (code "18") (name "/GAIN_CTL_A1") (class "Default")
      (node (ref "R23") (pin "6") (pinfunction "6_6") (pintype "passive"))
      (node (ref "U10") (pin "10") (pinfunction "A1_10") (pintype "input"))
    )
    (net (code "19") (name "/LE") (class "Default")
      (node (ref "R20") (pin "2") (pinfunction "2_2") (pintype "passive"))
      (node (ref "R23") (pin "4") (pinfunction "4_4") (pintype "passive"))
      (node (ref "U13") (pin "2") (pinfunction "A_2") (pintype "input"))
      (node (ref "U9") (pin "16") (pinfunction "LEB_16") (pintype "input"))
      (node (ref "U9") (pin "5") (pinfunction "LEA_5") (pintype "input"))
    )
    (net (code "20") (name "/MOSI") (class "Default")
      (node (ref "R31") (pin "5") (pinfunction "5_5") (pintype "passive"))
      (node (ref "U8") (pin "8") (pinfunction "DIN_8") (pintype "input"))
    )
    (net (code "21") (name "/OUTH_N") (class "Default")
      (node (ref "R33") (pin "2") (pinfunction "2_2") (pintype "passive"))
      (node (ref "U18") (pin "2") (pinfunction "~{D0}_2") (pintype "passive"))
      (node (ref "U9") (pin "3") (pinfunction "~{QA}_3") (pintype "output"))
    )
    (net (code "22") (name "/OUTH_P") (class "Default")
      (node (ref "R35") (pin "2") (pinfunction "2_2") (pintype "passive"))
      (node (ref "U18") (pin "1") (pinfunction "D0_1") (pintype "passive"))
      (node (ref "U9") (pin "2") (pinfunction "QA_2") (pintype "output"))
    )
    (net (code "23") (name "/OUTL_N") (class "Default")
      (node (ref "R28") (pin "2") (pinfunction "2_2") (pintype "passive"))
      (node (ref "U18") (pin "4") (pinfunction "~{D1}_4") (pintype "passive"))
      (node (ref "U9") (pin "18") (pinfunction "~{QB}_18") (pintype "output"))
    )
    (net (code "24") (name "/OUTL_P") (class "Default")
      (node (ref "R32") (pin "2") (pinfunction "2_2") (pintype "passive"))
      (node (ref "U18") (pin "3") (pinfunction "D1_3") (pintype "passive"))
      (node (ref "U9") (pin "19") (pinfunction "QB_19") (pintype "output"))
    )
    (net (code "25") (name "/S") (class "Default")
      (node (ref "C1") (pin "1") (pinfunction "1_1") (pintype "passive"))
      (node (ref "K1") (pin "1") (pinfunction "1_1") (pintype "passive"))
      (node (ref "K2") (pin "1") (pinfunction "1_1") (pintype "passive"))
      (node (ref "K3") (pin "1") (pinfunction "1_1") (pintype "passive"))
      (node (ref "S") (pin "1") (pinfunction "1_1") (pintype "passive"))
      (node (ref "S") (pin "10") (pinfunction "10_10") (pintype "passive"))
      (node (ref "S") (pin "2") (pinfunction "2_2") (pintype "passive"))
      (node (ref "S") (pin "3") (pinfunction "3_3") (pintype "passive"))
      (node (ref "S") (pin "4") (pinfunction "4_4") (pintype "passive"))
      (node (ref "S") (pin "5") (pinfunction "5_5") (pintype "passive"))
      (node (ref "S") (pin "6") (pinfunction "6_6") (pintype "passive"))
      (node (ref "S") (pin "7") (pinfunction "7_7") (pintype "passive"))
      (node (ref "S") (pin "8") (pinfunction "8_8") (pintype "passive"))
      (node (ref "S") (pin "9") (pinfunction "9_9") (pintype "passive"))
      (node (ref "S_BOT") (pin "1") (pinfunction "1_1") (pintype "passive"))
      (node (ref "S_BOT") (pin "10") (pinfunction "10_10") (pintype "passive"))
      (node (ref "S_BOT") (pin "2") (pinfunction "2_2") (pintype "passive"))
      (node (ref "S_BOT") (pin "3") (pinfunction "3_3") (pintype "passive"))
      (node (ref "S_BOT") (pin "4") (pinfunction "4_4") (pintype "passive"))
      (node (ref "S_BOT") (pin "5") (pinfunction "5_5") (pintype "passive"))
      (node (ref "S_BOT") (pin "6") (pinfunction "6_6") (pintype "passive"))
      (node (ref "S_BOT") (pin "7") (pinfunction "7_7") (pintype "passive"))
      (node (ref "S_BOT") (pin "8") (pinfunction "8_8") (pintype "passive"))
      (node (ref "S_BOT") (pin "9") (pinfunction "9_9") (pintype "passive"))
    )
    (net (code "26") (name "/SCK") (class "Default")
      (node (ref "R19") (pin "3") (pinfunction "3_3") (pintype "passive"))
      (node (ref "U8") (pin "7") (pinfunction "SCLK_7") (pintype "input"))
    )
    (net (code "27") (name "/STM_P2") (class "Default")
      (node (ref "R19") (pin "15") (pinfunction "15_15") (pintype "passive"))
      (node (ref "U16") (pin "2") (pinfunction "PF0-OSC_IN(PF0)_2") (pintype "bidirectional"))
    )
    (net (code "28") (name "/STM_P3") (class "Default")
      (node (ref "R19") (pin "14") (pinfunction "14_14") (pintype "passive"))
      (node (ref "U16") (pin "3") (pinfunction "PF1-OSC_OUT(PF1)_3") (pintype "bidirectional"))
    )
    (net (code "29") (name "/STM_P7") (class "Default")
      (node (ref "R19") (pin "10") (pinfunction "10_10") (pintype "passive"))
      (node (ref "U16") (pin "7") (pinfunction "PA0-TAMPER2-WKUP1_7") (pintype "bidirectional"))
    )
    (net (code "30") (name "/STM_P8") (class "Default")
      (node (ref "R19") (pin "9") (pinfunction "9_9") (pintype "passive"))
      (node (ref "U16") (pin "8") (pinfunction "PA1_8") (pintype "bidirectional"))
    )
    (net (code "31") (name "/STM_P9") (class "Default")
      (node (ref "R23") (pin "16") (pinfunction "16_16") (pintype "passive"))
      (node (ref "U16") (pin "9") (pinfunction "PA2_9") (pintype "bidirectional"))
    )
    (net (code "32") (name "/STM_P10") (class "Default")
      (node (ref "R23") (pin "15") (pinfunction "15_15") (pintype "passive"))
      (node (ref "U16") (pin "10") (pinfunction "PA3_10") (pintype "bidirectional"))
    )
    (net (code "33") (name "/STM_P11") (class "Default")
      (node (ref "R23") (pin "14") (pinfunction "14_14") (pintype "passive"))
      (node (ref "U16") (pin "11") (pinfunction "PA4_11") (pintype "bidirectional"))
    )
    (net (code "34") (name "/STM_P12") (class "Default")
      (node (ref "R23") (pin "13") (pinfunction "13_13") (pintype "passive"))
      (node (ref "U16") (pin "12") (pinfunction "PA5_12") (pintype "bidirectional"))
    )
    (net (code "35") (name "/STM_P13") (class "Default")
      (node (ref "R23") (pin "12") (pinfunction "12_12") (pintype "passive"))
      (node (ref "U16") (pin "13") (pinfunction "PA6_13") (pintype "bidirectional"))
    )
    (net (code "36") (name "/STM_P14") (class "Default")
      (node (ref "R23") (pin "11") (pinfunction "11_11") (pintype "passive"))
      (node (ref "U16") (pin "14") (pinfunction "PA7_14") (pintype "bidirectional"))
    )
    (net (code "37") (name "/STM_P15") (class "Default")
      (node (ref "R23") (pin "10") (pinfunction "10_10") (pintype "passive"))
      (node (ref "U16") (pin "15") (pinfunction "PB0_15") (pintype "bidirectional"))
    )
    (net (code "38") (name "/STM_P18") (class "Default")
      (node (ref "R31") (pin "15") (pinfunction "15_15") (pintype "passive"))
      (node (ref "U16") (pin "18") (pinfunction "PA8_18") (pintype "bidirectional"))
    )
    (net (code "39") (name "/STM_P19") (class "Default")
      (node (ref "R31") (pin "14") (pinfunction "14_14") (pintype "passive"))
      (node (ref "U16") (pin "19") (pinfunction "PA9_19") (pintype "bidirectional"))
    )
    (net (code "40") (name "/STM_P20") (class "Default")
      (node (ref "R31") (pin "13") (pinfunction "13_13") (pintype "passive"))
      (node (ref "U16") (pin "20") (pinfunction "PA10_20") (pintype "bidirectional"))
    )
    (net (code "41") (name "/STM_P21") (class "Default")
      (node (ref "R31") (pin "12") (pinfunction "12_12") (pintype "passive"))
      (node (ref "U16") (pin "21") (pinfunction "PA11_21") (pintype "bidirectional"))
    )
    (net (code "42") (name "/STM_P22") (class "Default")
      (node (ref "R31") (pin "11") (pinfunction "11_11") (pintype "passive"))
      (node (ref "U16") (pin "22") (pinfunction "PA12_22") (pintype "bidirectional"))
    )
    (net (code "43") (name "/STM_P23") (class "Default")
      (node (ref "R31") (pin "10") (pinfunction "10_10") (pintype "passive"))
      (node (ref "U16") (pin "23") (pinfunction "PA13_23") (pintype "bidirectional"))
    )
    (net (code "44") (name "/STM_P24") (class "Default")
      (node (ref "R31") (pin "9") (pinfunction "9_9") (pintype "passive"))
      (node (ref "U16") (pin "24") (pinfunction "PA14_24") (pintype "bidirectional"))
    )
    (net (code "45") (name "/STM_P25") (class "Default")
      (node (ref "R24") (pin "16") (pinfunction "16_16") (pintype "passive"))
      (node (ref "U16") (pin "25") (pinfunction "PA15_25") (pintype "bidirectional"))
    )
    (net (code "46") (name "/STM_P26") (class "Default")
      (node (ref "R24") (pin "15") (pinfunction "15_15") (pintype "passive"))
      (node (ref "U16") (pin "26") (pinfunction "PB3_26") (pintype "bidirectional"))
    )
    (net (code "47") (name "/STM_P27") (class "Default")
      (node (ref "R24") (pin "14") (pinfunction "14_14") (pintype "passive"))
      (node (ref "U16") (pin "27") (pinfunction "PB4_27") (pintype "bidirectional"))
    )
    (net (code "48") (name "/STM_P28") (class "Default")
      (node (ref "R24") (pin "13") (pinfunction "13_13") (pintype "passive"))
      (node (ref "U16") (pin "28") (pinfunction "PB5_28") (pintype "bidirectional"))
    )
    (net (code "49") (name "/STM_P29") (class "Default")
      (node (ref "R24") (pin "12") (pinfunction "12_12") (pintype "passive"))
      (node (ref "U16") (pin "29") (pinfunction "PB6_29") (pintype "bidirectional"))
    )
    (net (code "50") (name "/STM_P30") (class "Default")
      (node (ref "R24") (pin "11") (pinfunction "11_11") (pintype "passive"))
      (node (ref "U16") (pin "30") (pinfunction "PB7_30") (pintype "bidirectional"))
    )
    (net (code "51") (name "/SW1_CTL") (class "Default")
      (node (ref "R31") (pin "6") (pinfunction "6_6") (pintype "passive"))
      (node (ref "U20") (pin "3") (pinfunction "~{CLR}_3") (pintype "input"))
    )
    (net (code "52") (name "/SW1_STAT") (class "Default")
      (node (ref "Q11") (pin "4") (pinfunction "4_4") (pintype "passive"))
      (node (ref "R31") (pin "2") (pinfunction "2_2") (pintype "passive"))
      (node (ref "U20") (pin "5") (pinfunction "Q_5") (pintype "output"))
    )
    (net (code "53") (name "/SW2_CTL") (class "Default")
      (node (ref "R31") (pin "4") (pinfunction "4_4") (pintype "passive"))
      (node (ref "U17") (pin "3") (pinfunction "~{CLR}_3") (pintype "input"))
    )
    (net (code "54") (name "/SW2_STAT") (class "Default")
      (node (ref "Q10") (pin "2") (pinfunction "2_2") (pintype "passive"))
      (node (ref "R23") (pin "7") (pinfunction "7_7") (pintype "passive"))
      (node (ref "U17") (pin "5") (pinfunction "Q_5") (pintype "output"))
    )
    (net (code "55") (name "/TAB") (class "Default")
      (node (ref "J3") (pin "1") (pinfunction "1_1") (pintype "passive"))
      (node (ref "TAB") (pin "1") (pinfunction "1_1") (pintype "passive"))
      (node (ref "TAB") (pin "10") (pinfunction "10_10") (pintype "passive"))
      (node (ref "TAB") (pin "2") (pinfunction "2_2") (pintype "passive"))
      (node (ref "TAB") (pin "3") (pinfunction "3_3") (pintype "passive"))
      (node (ref "TAB") (pin "4") (pinfunction "4_4") (pintype "passive"))
      (node (ref "TAB") (pin "5") (pinfunction "5_5") (pintype "passive"))
      (node (ref "TAB") (pin "6") (pinfunction "6_6") (pintype "passive"))
      (node (ref "TAB") (pin "7") (pinfunction "7_7") (pintype "passive"))
      (node (ref "TAB") (pin "8") (pinfunction "8_8") (pintype "passive"))
      (node (ref "TAB") (pin "9") (pinfunction "9_9") (pintype "passive"))
      (node (ref "TAB_BOT") (pin "1") (pinfunction "1_1") (pintype "passive"))
      (node (ref "TAB_BOT") (pin "10") (pinfunction "10_10") (pintype "passive"))
      (node (ref "TAB_BOT") (pin "2") (pinfunction "2_2") (pintype "passive"))
      (node (ref "TAB_BOT") (pin "3") (pinfunction "3_3") (pintype "passive"))
      (node (ref "TAB_BOT") (pin "4") (pinfunction "4_4") (pintype "passive"))
      (node (ref "TAB_BOT") (pin "5") (pinfunction "5_5") (pintype "passive"))
      (node (ref "TAB_BOT") (pin "6") (pinfunction "6_6") (pintype "passive"))
      (node (ref "TAB_BOT") (pin "7") (pinfunction "7_7") (pintype "passive"))
      (node (ref "TAB_BOT") (pin "8") (pinfunction "8_8") (pintype "passive"))
      (node (ref "TAB_BOT") (pin "9") (pinfunction "9_9") (pintype "passive"))
    )
    (net (code "56") (name "/TCK") (class "Default")
      (node (ref "J8") (pin "4") (pinfunction "4_4") (pintype "passive"))
      (node (ref "R31") (pin "8") (pinfunction "8_8") (pintype "passive"))
    )
    (net (code "57") (name "/TDI") (class "Default")
      (node (ref "J8") (pin "8") (pinfunction "8_8") (pintype "passive"))
      (node (ref "R24") (pin "2") (pinfunction "2_2") (pintype "passive"))
    )
    (net (code "58") (name "/TDO") (class "Default")
      (node (ref "J8") (pin "6") (pinfunction "6_6") (pintype "passive"))
      (node (ref "R24") (pin "1") (pinfunction "1_1") (pintype "passive"))
    )
    (net (code "59") (name "/TIA_RCTL") (class "Default")
      (node (ref "Q1") (pin "1") (pinfunction "G_1") (pintype "passive"))
      (node (ref "R19") (pin "8") (pinfunction "8_8") (pintype "passive"))
    )
    (net (code "60") (name "/TMS") (class "Default")
      (node (ref "J8") (pin "2") (pinfunction "2_2") (pintype "passive"))
      (node (ref "R31") (pin "7") (pinfunction "7_7") (pintype "passive"))
    )
    (net (code "61") (name "/V_GRD") (class "Default")
      (node (ref "R42") (pin "1") (pinfunction "1_1") (pintype "passive"))
      (node (ref "U22") (pin "1") (pinfunction "OUT_1") (pintype "output"))
      (node (ref "U22") (pin "4") (pinfunction "IN-_4") (pintype "input"))
    )
    (net (code "62") (name "/Vin_COMP") (class "Default")
      (node (ref "TP1") (pin "1") (pinfunction "1_1") (pintype "passive"))
      (node (ref "U10") (pin "8") (pinfunction "D_8") (pintype "passive"))
      (node (ref "U11") (pin "1") (pinfunction "OUT_1") (pintype "output"))
      (node (ref "U9") (pin "13") (pinfunction "-INB_13") (pintype "input"))
      (node (ref "U9") (pin "9") (pinfunction "+INA_9") (pintype "input"))
    )
    (net (code "63") (name "/Vsource") (class "Default")
      (node (ref "C30") (pin "2") (pinfunction "2_2") (pintype "passive"))
      (node (ref "C31") (pin "1") (pinfunction "1_1") (pintype "passive"))
      (node (ref "C32") (pin "1") (pinfunction "1_1") (pintype "passive"))
      (node (ref "L3") (pin "1") (pinfunction "1_1") (pintype "passive"))
      (node (ref "R10") (pin "2") (pinfunction "2_2") (pintype "passive"))
      (node (ref "R11") (pin "2") (pinfunction "2_2") (pintype "passive"))
      (node (ref "R12") (pin "2") (pinfunction "2_2") (pintype "passive"))
      (node (ref "U11") (pin "4") (pinfunction "IN-_4") (pintype "input"))
    )
    (net (code "64") (name "/Vth_H") (class "Default")
      (node (ref "TP2") (pin "1") (pinfunction "1_1") (pintype "passive"))
      (node (ref "U8") (pin "2") (pinfunction "VOUTB_2") (pintype "tri_state"))
      (node (ref "U9") (pin "8") (pinfunction "-INA_8") (pintype "input"))
    )
    (net (code "65") (name "/Vth_L") (class "Default")
      (node (ref "TP3") (pin "1") (pinfunction "1_1") (pintype "passive"))
      (node (ref "U8") (pin "1") (pinfunction "VOUTA_1") (pintype "tri_state"))
      (node (ref "U9") (pin "12") (pinfunction "+INB_12") (pintype "input"))
    )
    (net (code "66") (name "/nTRST") (class "Default")
      (node (ref "J8") (pin "10") (pinfunction "10_10") (pintype "passive"))
      (node (ref "R24") (pin "3") (pinfunction "3_3") (pintype "passive"))
    )
    (net (code "67") (name "/~{CS}_DAC") (class "Default")
      (node (ref "R23") (pin "2") (pinfunction "2_2") (pintype "passive"))
      (node (ref "U8") (pin "6") (pinfunction "~{SYNC}_6") (pintype "input"))
    )
    (net (code "68") (name "/~{CS}_DDS") (class "Default")
      (node (ref "R23") (pin "1") (pinfunction "1_1") (pintype "passive"))
    )
    (net (code "69") (name "/~{LE}") (class "Default")
      (node (ref "U13") (pin "4") (pinfunction "Y_4") (pintype "output"))
      (node (ref "U9") (pin "15") (pinfunction "~{LEB}_15") (pintype "input"))
      (node (ref "U9") (pin "6") (pinfunction "~{LEA}_6") (pintype "input"))
    )
    (net (code "70") (name "/~{RESET}") (class "Default")
      (node (ref "C53") (pin "1") (pinfunction "1_1") (pintype "passive"))
      (node (ref "C69") (pin "1") (pinfunction "1_1") (pintype "passive"))
      (node (ref "R38") (pin "1") (pinfunction "1_1") (pintype "passive"))
      (node (ref "SW1") (pin "1") (pinfunction "1_1") (pintype "passive"))
      (node (ref "U16") (pin "4") (pinfunction "NRST_4") (pintype "bidirectional"))
    )
    (net (code "71") (name "5V_IN") (class "Default")
      (node (ref "C49") (pin "1") (pinfunction "1_1") (pintype "passive"))
      (node (ref "D1") (pin "1") (pinfunction "K_1") (pintype "passive"))
      (node (ref "D2") (pin "1") (pinfunction "K_1") (pintype "passive"))
      (node (ref "D3") (pin "1") (pinfunction "K_1") (pintype "passive"))
      (node (ref "D5") (pin "1") (pinfunction "K_1") (pintype "passive"))
      (node (ref "K1") (pin "4") (pinfunction "4_4") (pintype "passive"))
      (node (ref "K2") (pin "4") (pinfunction "4_4") (pintype "passive"))
      (node (ref "K3") (pin "4") (pinfunction "4_4") (pintype "passive"))
      (node (ref "R21") (pin "2") (pinfunction "2_2") (pintype "passive"))
      (node (ref "TP5") (pin "1") (pinfunction "1_1") (pintype "passive"))
    )
    (net (code "72") (name "AVDD") (class "Default")
      (node (ref "C33") (pin "1") (pinfunction "1_1") (pintype "passive"))
      (node (ref "C34") (pin "1") (pinfunction "1_1") (pintype "passive"))
      (node (ref "C41") (pin "2") (pinfunction "2_2") (pintype "passive"))
      (node (ref "C42") (pin "1") (pinfunction "1_1") (pintype "passive"))
      (node (ref "C45") (pin "2") (pinfunction "2_2") (pintype "passive"))
      (node (ref "C46") (pin "1") (pinfunction "1_1") (pintype "passive"))
      (node (ref "C73") (pin "1") (pinfunction "1_1") (pintype "passive"))
      (node (ref "C74") (pin "2") (pinfunction "2_2") (pintype "passive"))
      (node (ref "R15") (pin "1") (pinfunction "1_1") (pintype "passive"))
      (node (ref "R16") (pin "1") (pinfunction "1_1") (pintype "passive"))
      (node (ref "R18") (pin "1") (pinfunction "1_1") (pintype "passive"))
      (node (ref "U10") (pin "6") (pinfunction "VDD_6") (pintype "power_in"))
      (node (ref "U11") (pin "6") (pinfunction "V+_6") (pintype "passive"))
      (node (ref "U22") (pin "6") (pinfunction "V+_6") (pintype "passive"))
      (node (ref "U9") (pin "7") (pinfunction "VCCI_7") (pintype "passive"))
    )
    (net (code "73") (name "DVDD") (class "Default")
      (node (ref "C27") (pin "1") (pinfunction "1_1") (pintype "passive"))
      (node (ref "C37") (pin "1") (pinfunction "1_1") (pintype "passive"))
      (node (ref "C39") (pin "2") (pinfunction "2_2") (pintype "passive"))
      (node (ref "C40") (pin "2") (pinfunction "2_2") (pintype "passive"))
      (node (ref "C43") (pin "2") (pinfunction "2_2") (pintype "passive"))
      (node (ref "C44") (pin "2") (pinfunction "2_2") (pintype "passive"))
      (node (ref "C47") (pin "1") (pinfunction "1_1") (pintype "passive"))
      (node (ref "C48") (pin "1") (pinfunction "1_1") (pintype "passive"))
      (node (ref "C52") (pin "1") (pinfunction "1_1") (pintype "passive"))
      (node (ref "C55") (pin "1") (pinfunction "1_1") (pintype "passive"))
      (node (ref "C56") (pin "1") (pinfunction "1_1") (pintype "passive"))
      (node (ref "C60") (pin "1") (pinfunction "1_1") (pintype "passive"))
      (node (ref "C63") (pin "1") (pinfunction "1_1") (pintype "passive"))
      (node (ref "C64") (pin "1") (pinfunction "1_1") (pintype "passive"))
      (node (ref "C65") (pin "1") (pinfunction "1_1") (pintype "passive"))
      (node (ref "C66") (pin "2") (pinfunction "2_2") (pintype "passive"))
      (node (ref "C68") (pin "1") (pinfunction "1_1") (pintype "passive"))
      (node (ref "J8") (pin "1") (pinfunction "1_1") (pintype "passive"))
      (node (ref "R20") (pin "1") (pinfunction "1_1") (pintype "passive"))
      (node (ref "R26") (pin "2") (pinfunction "2_2") (pintype "passive"))
      (node (ref "R36") (pin "2") (pinfunction "2_2") (pintype "passive"))
      (node (ref "R38") (pin "2") (pinfunction "2_2") (pintype "passive"))
      (node (ref "R9") (pin "2") (pinfunction "2_2") (pintype "passive"))
      (node (ref "U13") (pin "5") (pinfunction "VCC_5") (pintype "power_in"))
      (node (ref "U16") (pin "1") (pinfunction "VDD_1_1") (pintype "power_in"))
      (node (ref "U16") (pin "17") (pinfunction "VDD_2_17") (pintype "power_in"))
      (node (ref "U16") (pin "5") (pinfunction "VDDA/VREF+_5") (pintype "power_in"))
      (node (ref "U17") (pin "8") (pinfunction "VCC_8") (pintype "passive"))
      (node (ref "U18") (pin "8") (pinfunction "VCC_8") (pintype "passive"))
      (node (ref "U19") (pin "5") (pinfunction "VCC_5") (pintype "power_in"))
      (node (ref "U20") (pin "8") (pinfunction "VCC_8") (pintype "passive"))
      (node (ref "U5") (pin "1") (pinfunction "VDD1_1") (pintype "power_in"))
      (node (ref "U5") (pin "3") (pinfunction "VDD1_3") (pintype "power_in"))
      (node (ref "U8") (pin "9") (pinfunction "VDD_9") (pintype "power_in"))
      (node (ref "U9") (pin "1") (pinfunction "VCCO_1") (pintype "passive"))
      (node (ref "U9") (pin "17") (pinfunction "VCCO_17") (pintype "passive"))
      (node (ref "U9") (pin "20") (pinfunction "VCCO_20") (pintype "passive"))
      (node (ref "U9") (pin "4") (pinfunction "VCCO_4") (pintype "passive"))
    )
    (net (code "74") (name "GND") (class "Default")
      (node (ref "C27") (pin "2") (pinfunction "2_2") (pintype "passive"))
      (node (ref "C33") (pin "2") (pinfunction "2_2") (pintype "passive"))
      (node (ref "C34") (pin "2") (pinfunction "2_2") (pintype "passive"))
      (node (ref "C37") (pin "2") (pinfunction "2_2") (pintype "passive"))
      (node (ref "C38") (pin "2") (pinfunction "2_2") (pintype "passive"))
      (node (ref "C39") (pin "1") (pinfunction "1_1") (pintype "passive"))
      (node (ref "C40") (pin "1") (pinfunction "1_1") (pintype "passive"))
      (node (ref "C41") (pin "1") (pinfunction "1_1") (pintype "passive"))
      (node (ref "C42") (pin "2") (pinfunction "2_2") (pintype "passive"))
      (node (ref "C43") (pin "1") (pinfunction "1_1") (pintype "passive"))
      (node (ref "C44") (pin "1") (pinfunction "1_1") (pintype "passive"))
      (node (ref "C45") (pin "1") (pinfunction "1_1") (pintype "passive"))
      (node (ref "C46") (pin "2") (pinfunction "2_2") (pintype "passive"))
      (node (ref "C47") (pin "2") (pinfunction "2_2") (pintype "passive"))
      (node (ref "C48") (pin "2") (pinfunction "2_2") (pintype "passive"))
      (node (ref "C49") (pin "2") (pinfunction "2_2") (pintype "passive"))
      (node (ref "C52") (pin "2") (pinfunction "2_2") (pintype "passive"))
      (node (ref "C53") (pin "2") (pinfunction "2_2") (pintype "passive"))
      (node (ref "C55") (pin "2") (pinfunction "2_2") (pintype "passive"))
      (node (ref "C56") (pin "2") (pinfunction "2_2") (pintype "passive"))
      (node (ref "C57") (pin "1") (pinfunction "1_1") (pintype "passive"))
      (node (ref "C58") (pin "2") (pinfunction "2_2") (pintype "passive"))
      (node (ref "C59") (pin "2") (pinfunction "2_2") (pintype "passive"))
      (node (ref "C60") (pin "2") (pinfunction "2_2") (pintype "passive"))
      (node (ref "C61") (pin "1") (pinfunction "1_1") (pintype "passive"))
      (node (ref "C63") (pin "2") (pinfunction "2_2") (pintype "passive"))
      (node (ref "C64") (pin "2") (pinfunction "2_2") (pintype "passive"))
      (node (ref "C65") (pin "2") (pinfunction "2_2") (pintype "passive"))
      (node (ref "C66") (pin "1") (pinfunction "1_1") (pintype "passive"))
      (node (ref "C68") (pin "2") (pinfunction "2_2") (pintype "passive"))
      (node (ref "C73") (pin "2") (pinfunction "2_2") (pintype "passive"))
      (node (ref "C74") (pin "1") (pinfunction "1_1") (pintype "passive"))
      (node (ref "C75") (pin "2") (pinfunction "2_2") (pintype "passive"))
      (node (ref "C76") (pin "1") (pinfunction "1_1") (pintype "passive"))
      (node (ref "C76") (pin "2") (pinfunction "2_2") (pintype "passive"))
      (node (ref "C78") (pin "1") (pinfunction "1_1") (pintype "passive"))
      (node (ref "C78") (pin "2") (pinfunction "2_2") (pintype "passive"))
      (node (ref "D5") (pin "2") (pinfunction "A_2") (pintype "passive"))
      (node (ref "D7") (pin "2") (pinfunction "C_2") (pintype "passive"))
      (node (ref "D8") (pin "1") (pinfunction "1_1") (pintype "passive"))
      (node (ref "J1") (pin "2") (pinfunction "2_2") (pintype "passive"))
      (node (ref "J1") (pin "3") (pinfunction "3_3") (pintype "passive"))
      (node (ref "J1") (pin "4") (pinfunction "4_4") (pintype "passive"))
      (node (ref "J2") (pin "2") (pinfunction "2_2") (pintype "passive"))
      (node (ref "J2") (pin "3") (pinfunction "3_3") (pintype "passive"))
      (node (ref "J2") (pin "4") (pinfunction "4_4") (pintype "passive"))
      (node (ref "J3") (pin "2") (pinfunction "2_2") (pintype "passive"))
      (node (ref "J3") (pin "3") (pinfunction "3_3") (pintype "passive"))
      (node (ref "J3") (pin "4") (pinfunction "4_4") (pintype "passive"))
      (node (ref "J4") (pin "2") (pinfunction "2_2") (pintype "passive"))
      (node (ref "J4") (pin "3") (pinfunction "3_3") (pintype "passive"))
      (node (ref "J4") (pin "4") (pinfunction "4_4") (pintype "passive"))
      (node (ref "J5") (pin "4") (pinfunction "GND_4") (pintype "passive"))
      (node (ref "J5") (pin "5") (pinfunction "SHLD1_5") (pintype "passive"))
      (node (ref "J5") (pin "6") (pinfunction "SHLD2_6") (pintype "passive"))
      (node (ref "J7") (pin "2") (pinfunction "2_2") (pintype "passive"))
      (node (ref "J7") (pin "3") (pinfunction "3_3") (pintype "passive"))
      (node (ref "J7") (pin "SH1") (pinfunction "SH1_SH1") (pintype "passive"))
      (node (ref "J7") (pin "SH2") (pinfunction "SH2_SH2") (pintype "passive"))
      (node (ref "J8") (pin "3") (pinfunction "3_3") (pintype "passive"))
      (node (ref "J8") (pin "5") (pinfunction "5_5") (pintype "passive"))
      (node (ref "J8") (pin "9") (pinfunction "9_9") (pintype "passive"))
      (node (ref "Q1") (pin "2") (pinfunction "G_2") (pintype "passive"))
      (node (ref "Q10") (pin "1") (pinfunction "1_1") (pintype "passive"))
      (node (ref "Q10") (pin "3") (pinfunction "3_3") (pintype "passive"))
      (node (ref "Q11") (pin "1") (pinfunction "1_1") (pintype "passive"))
      (node (ref "Q11") (pin "3") (pinfunction "3_3") (pintype "passive"))
      (node (ref "Q2") (pin "2") (pinfunction "G_2") (pintype "passive"))
      (node (ref "Q3") (pin "2") (pinfunction "G_2") (pintype "passive"))
      (node (ref "Q7") (pin "2") (pinfunction "S_2") (pintype "passive"))
      (node (ref "Q8") (pin "1") (pinfunction "1_1") (pintype "passive"))
      (node (ref "Q9") (pin "2") (pinfunction "S_2") (pintype "passive"))
      (node (ref "R13") (pin "2") (pinfunction "2_2") (pintype "passive"))
      (node (ref "R25") (pin "2") (pinfunction "2_2") (pintype "passive"))
      (node (ref "R29") (pin "1") (pinfunction "1_1") (pintype "passive"))
      (node (ref "R34") (pin "1") (pinfunction "1_1") (pintype "passive"))
      (node (ref "R41") (pin "2") (pinfunction "2_2") (pintype "passive"))
      (node (ref "SW1") (pin "2") (pinfunction "2_2") (pintype "passive"))
      (node (ref "U10") (pin "3") (pinfunction "GND_3") (pintype "power_in"))
      (node (ref "U11") (pin "2") (pinfunction "V-_2") (pintype "passive"))
      (node (ref "U13") (pin "3") (pinfunction "GND_3") (pintype "power_in"))
      (node (ref "U15") (pin "2") (pinfunction "GND_2") (pintype "power_in"))
      (node (ref "U15") (pin "25") (pinfunction "GND_25") (pintype "power_in"))
      (node (ref "U16") (pin "16") (pinfunction "VSS_2_16") (pintype "power_in"))
      (node (ref "U16") (pin "32") (pinfunction "VSS_1_32") (pintype "power_in"))
      (node (ref "U16") (pin "33") (pinfunction "EP_33") (pintype "passive"))
      (node (ref "U16") (pin "6") (pinfunction "VSSA/VREF-_6") (pintype "power_in"))
      (node (ref "U17") (pin "1") (pinfunction "~{A}_1") (pintype "input"))
      (node (ref "U17") (pin "4") (pinfunction "GND_4") (pintype "passive"))
      (node (ref "U18") (pin "5") (pinfunction "GND_5") (pintype "passive"))
      (node (ref "U19") (pin "3") (pinfunction "GND_3") (pintype "power_in"))
      (node (ref "U20") (pin "1") (pinfunction "~{A}_1") (pintype "input"))
      (node (ref "U20") (pin "4") (pinfunction "GND_4") (pintype "passive"))
      (node (ref "U22") (pin "2") (pinfunction "V-_2") (pintype "passive"))
      (node (ref "U5") (pin "4") (pinfunction "GND1_4") (pintype "power_in"))
      (node (ref "U8") (pin "11") (pinfunction "EP_11") (pintype "power_in"))
      (node (ref "U8") (pin "3") (pinfunction "GND_3") (pintype "power_in"))
      (node (ref "U8") (pin "4") (pinfunction "~{LDAC}_4") (pintype "input"))
      (node (ref "U9") (pin "14") (pinfunction "AGND_14") (pintype "passive"))
    )
    (net (code "75") (name "GND_F") (class "Default")
      (node (ref "C25") (pin "2") (pinfunction "2_2") (pintype "passive"))
      (node (ref "D12") (pin "1") (pinfunction "K_1") (pintype "passive"))
      (node (ref "D13") (pin "2") (pinfunction "A_2") (pintype "passive"))
      (node (ref "Q5") (pin "2") (pinfunction "S_2") (pintype "passive"))
      (node (ref "U5") (pin "5") (pinfunction "GND2_5") (pintype "power_in"))
      (node (ref "U5") (pin "7") (pinfunction "GND2_7") (pintype "power_in"))
    )
    (net (code "76") (name "Net-(C24-Pad2)") (class "Default")
      (node (ref "C24") (pin "2") (pinfunction "2_2") (pintype "passive"))
      (node (ref "R13") (pin "1") (pinfunction "1_1") (pintype "passive"))
    )
    (net (code "77") (name "Net-(C69-Pad2)") (class "Default")
      (node (ref "C69") (pin "2") (pinfunction "2_2") (pintype "passive"))
      (node (ref "R41") (pin "1") (pinfunction "1_1") (pintype "passive"))
    )
    (net (code "78") (name "Net-(C75-Pad1)") (class "Default")
      (node (ref "C75") (pin "1") (pinfunction "1_1") (pintype "passive"))
      (node (ref "R42") (pin "2") (pinfunction "2_2") (pintype "passive"))
    )
    (net (code "79") (name "Net-(D1-A)") (class "Default")
      (node (ref "D1") (pin "2") (pinfunction "A_2") (pintype "passive"))
      (node (ref "K3") (pin "3") (pinfunction "3_3") (pintype "passive"))
      (node (ref "Q1") (pin "3") (pinfunction "G_3") (pintype "passive"))
    )
    (net (code "80") (name "Net-(D2-A)") (class "Default")
      (node (ref "D2") (pin "2") (pinfunction "A_2") (pintype "passive"))
      (node (ref "K2") (pin "3") (pinfunction "3_3") (pintype "passive"))
      (node (ref "Q2") (pin "3") (pinfunction "G_3") (pintype "passive"))
    )
    (net (code "81") (name "Net-(D3-A)") (class "Default")
      (node (ref "D3") (pin "2") (pinfunction "A_2") (pintype "passive"))
      (node (ref "K1") (pin "3") (pinfunction "3_3") (pintype "passive"))
      (node (ref "Q3") (pin "3") (pinfunction "G_3") (pintype "passive"))
    )
    (net (code "82") (name "Net-(D6-A)") (class "Default")
      (node (ref "D6") (pin "2") (pinfunction "A_2") (pintype "passive"))
      (node (ref "D7") (pin "1") (pinfunction "C_1") (pintype "passive"))
      (node (ref "J6") (pin "2") (pinfunction "2_2") (pintype "passive"))
    )
    (net (code "83") (name "Net-(D6-K)") (class "Default")
      (node (ref "D6") (pin "1") (pinfunction "K_1") (pintype "passive"))
      (node (ref "R21") (pin "1") (pinfunction "1_1") (pintype "passive"))
    )
    (net (code "84") (name "Net-(D9-A)") (class "Default")
      (node (ref "D9") (pin "2") (pinfunction "A_2") (pintype "passive"))
      (node (ref "Q7") (pin "3") (pinfunction "G_3") (pintype "passive"))
      (node (ref "R27") (pin "2") (pinfunction "2_2") (pintype "passive"))
      (node (ref "U18") (pin "6") (pinfunction "Q1_6") (pintype "output"))
    )
    (net (code "85") (name "Net-(D10-A)") (class "Default")
      (node (ref "D10") (pin "2") (pinfunction "A_2") (pintype "passive"))
      (node (ref "Q9") (pin "3") (pinfunction "G_3") (pintype "passive"))
      (node (ref "R39") (pin "2") (pinfunction "2_2") (pintype "passive"))
      (node (ref "U18") (pin "7") (pinfunction "Q0_7") (pintype "output"))
    )
    (net (code "86") (name "Net-(D12-A)") (class "Default")
      (node (ref "C24") (pin "1") (pinfunction "1_1") (pintype "passive"))
      (node (ref "D12") (pin "2") (pinfunction "A_2") (pintype "passive"))
      (node (ref "D13") (pin "1") (pinfunction "K_1") (pintype "passive"))
      (node (ref "L2") (pin "1") (pinfunction "1_1") (pintype "passive"))
      (node (ref "Q4") (pin "2") (pinfunction "S_2") (pintype "passive"))
      (node (ref "Q4") (pin "3") (pinfunction "S_3") (pintype "passive"))
      (node (ref "Q4") (pin "4") (pinfunction "S_4") (pintype "passive"))
      (node (ref "Q4") (pin "5") (pinfunction "S_5") (pintype "passive"))
      (node (ref "Q4") (pin "6") (pinfunction "S_6") (pintype "passive"))
      (node (ref "Q4") (pin "7") (pinfunction "S_7") (pintype "passive"))
    )
    (net (code "87") (name "Net-(J4-Pad1)") (class "Default")
      (node (ref "J4") (pin "1") (pinfunction "1_1") (pintype "passive"))
      (node (ref "K2") (pin "2") (pinfunction "2_2") (pintype "passive"))
    )
    (net (code "88") (name "Net-(J6-Pad1)") (class "Default")
      (node (ref "J6") (pin "1") (pinfunction "1_1") (pintype "passive"))
      (node (ref "J7") (pin "1") (pinfunction "1_1") (pintype "passive"))
    )
    (net (code "89") (name "Net-(K3-Pad2)") (class "Default")
      (node (ref "K3") (pin "2") (pinfunction "2_2") (pintype "passive"))
      (node (ref "L2") (pin "2") (pinfunction "2_2") (pintype "passive"))
    )
    (net (code "90") (name "Net-(L3-Pad2)") (class "Default")
      (node (ref "L3") (pin "2") (pinfunction "2_2") (pintype "passive"))
      (node (ref "Q6") (pin "2") (pinfunction "S_2") (pintype "passive"))
      (node (ref "Q6") (pin "3") (pinfunction "S_3") (pintype "passive"))
      (node (ref "Q6") (pin "4") (pinfunction "S_4") (pintype "passive"))
      (node (ref "Q6") (pin "5") (pinfunction "S_5") (pintype "passive"))
      (node (ref "Q6") (pin "6") (pinfunction "S_6") (pintype "passive"))
      (node (ref "Q6") (pin "7") (pinfunction "S_7") (pintype "passive"))
    )
    (net (code "91") (name "Net-(Q4-D)") (class "Default")
      (node (ref "Q4") (pin "8") (pinfunction "D_8") (pintype "passive"))
      (node (ref "Q6") (pin "8") (pinfunction "D_8") (pintype "passive"))
    )
    (net (code "92") (name "Net-(Q4-G)") (class "Default")
      (node (ref "Q4") (pin "1") (pinfunction "G_1") (pintype "passive"))
      (node (ref "Q5") (pin "3") (pinfunction "D_3") (pintype "passive"))
      (node (ref "R8") (pin "1") (pinfunction "1_1") (pintype "passive"))
    )
    (net (code "93") (name "Net-(Q5-G)") (class "Default")
      (node (ref "Q5") (pin "1") (pinfunction "G_1") (pintype "passive"))
      (node (ref "U5") (pin "6") (pinfunction "VO_6") (pintype "output"))
    )
    (net (code "94") (name "Net-(Q6-G)") (class "Default")
      (node (ref "Q10") (pin "4") (pinfunction "4_4") (pintype "passive"))
      (node (ref "Q10") (pin "7") (pinfunction "7_7") (pintype "passive"))
      (node (ref "Q10") (pin "8") (pinfunction "8_8") (pintype "passive"))
      (node (ref "Q11") (pin "5") (pinfunction "5_5") (pintype "passive"))
      (node (ref "Q11") (pin "6") (pinfunction "6_6") (pintype "passive"))
      (node (ref "Q11") (pin "7") (pinfunction "7_7") (pintype "passive"))
      (node (ref "Q11") (pin "8") (pinfunction "8_8") (pintype "passive"))
      (node (ref "Q6") (pin "1") (pinfunction "G_1") (pintype "passive"))
      (node (ref "Q7") (pin "1") (pinfunction "D_1") (pintype "passive"))
      (node (ref "Q9") (pin "1") (pinfunction "D_1") (pintype "passive"))
      (node (ref "R37") (pin "2") (pinfunction "2_2") (pintype "passive"))
    )
    (net (code "95") (name "Net-(Q8-Pad4)") (class "Default")
      (node (ref "Q8") (pin "4") (pinfunction "4_4") (pintype "passive"))
      (node (ref "Q8") (pin "7") (pinfunction "7_7") (pintype "passive"))
      (node (ref "Q8") (pin "8") (pinfunction "8_8") (pintype "passive"))
      (node (ref "R30") (pin "2") (pinfunction "2_2") (pintype "passive"))
    )
    (net (code "96") (name "Net-(Q8-Pad5)") (class "Default")
      (node (ref "Q8") (pin "5") (pinfunction "5_5") (pintype "passive"))
      (node (ref "Q8") (pin "6") (pinfunction "6_6") (pintype "passive"))
      (node (ref "R37") (pin "1") (pinfunction "1_1") (pintype "passive"))
    )
    (net (code "97") (name "Net-(R28-Pad1)") (class "Default")
      (node (ref "R28") (pin "1") (pinfunction "1_1") (pintype "passive"))
      (node (ref "R29") (pin "2") (pinfunction "2_2") (pintype "passive"))
      (node (ref "R32") (pin "1") (pinfunction "1_1") (pintype "passive"))
    )
    (net (code "98") (name "Net-(R33-Pad1)") (class "Default")
      (node (ref "R33") (pin "1") (pinfunction "1_1") (pintype "passive"))
      (node (ref "R34") (pin "2") (pinfunction "2_2") (pintype "passive"))
      (node (ref "R35") (pin "1") (pinfunction "1_1") (pintype "passive"))
    )
    (net (code "99") (name "Net-(U5-VI)") (class "Default")
      (node (ref "Q10") (pin "5") (pinfunction "5_5") (pintype "passive"))
      (node (ref "Q10") (pin "6") (pinfunction "6_6") (pintype "passive"))
      (node (ref "R9") (pin "1") (pinfunction "1_1") (pintype "passive"))
      (node (ref "U5") (pin "2") (pinfunction "VI_2") (pintype "input"))
    )
    (net (code "100") (name "Net-(U9A-HYSA)") (class "Default")
      (node (ref "R16") (pin "2") (pinfunction "2_2") (pintype "passive"))
      (node (ref "U9") (pin "10") (pinfunction "HYSA_10") (pintype "input"))
    )
    (net (code "101") (name "Net-(U9B-HYSB)") (class "Default")
      (node (ref "R15") (pin "2") (pinfunction "2_2") (pintype "passive"))
      (node (ref "U9") (pin "11") (pinfunction "HYSB_11") (pintype "input"))
    )
    (net (code "102") (name "Net-(U10-EN)") (class "Default")
      (node (ref "R18") (pin "2") (pinfunction "2_2") (pintype "passive"))
      (node (ref "U10") (pin "5") (pinfunction "EN_5") (pintype "input"))
    )
    (net (code "103") (name "Net-(U10-S2)") (class "Default")
      (node (ref "C32") (pin "2") (pinfunction "2_2") (pintype "passive"))
      (node (ref "R12") (pin "1") (pinfunction "1_1") (pintype "passive"))
      (node (ref "U10") (pin "9") (pinfunction "S2_9") (pintype "passive"))
    )
    (net (code "104") (name "Net-(U10-S3)") (class "Default")
      (node (ref "C30") (pin "1") (pinfunction "1_1") (pintype "passive"))
      (node (ref "R10") (pin "1") (pinfunction "1_1") (pintype "passive"))
      (node (ref "U10") (pin "4") (pinfunction "S3_4") (pintype "passive"))
    )
    (net (code "105") (name "Net-(U10-S4)") (class "Default")
      (node (ref "C31") (pin "2") (pinfunction "2_2") (pintype "passive"))
      (node (ref "R11") (pin "1") (pinfunction "1_1") (pintype "passive"))
      (node (ref "U10") (pin "7") (pinfunction "S4_7") (pintype "passive"))
    )
    (net (code "106") (name "Net-(U15-VDD)") (class "Default")
      (node (ref "C59") (pin "1") (pinfunction "1_1") (pintype "passive"))
      (node (ref "C61") (pin "2") (pinfunction "2_2") (pintype "passive"))
      (node (ref "R22") (pin "2") (pinfunction "2_2") (pintype "passive"))
      (node (ref "U15") (pin "5") (pinfunction "VIO_5") (pintype "power_in"))
      (node (ref "U15") (pin "6") (pinfunction "VDD_6") (pintype "power_in"))
    )
    (net (code "107") (name "Net-(U15-VPP)") (class "Default")
      (node (ref "C57") (pin "2") (pinfunction "2_2") (pintype "passive"))
      (node (ref "U15") (pin "16") (pinfunction "VPP_16") (pintype "passive"))
    )
    (net (code "108") (name "Net-(U15-~{RST})") (class "Default")
      (node (ref "R22") (pin "1") (pinfunction "1_1") (pintype "passive"))
      (node (ref "U15") (pin "9") (pinfunction "~{RST}_9") (pintype "bidirectional"))
    )
    (net (code "109") (name "Net-(U16-BOOT0)") (class "Default")
      (node (ref "R25") (pin "1") (pinfunction "1_1") (pintype "passive"))
      (node (ref "U16") (pin "31") (pinfunction "BOOT0_31") (pintype "input"))
    )
    (net (code "110") (name "Net-(U17-CEXT)") (class "Default")
      (node (ref "C62") (pin "2") (pinfunction "2_2") (pintype "passive"))
      (node (ref "U17") (pin "6") (pinfunction "CEXT_6") (pintype "passive"))
    )
    (net (code "111") (name "Net-(U17-REXT{slash}CEXT)") (class "Default")
      (node (ref "C62") (pin "1") (pinfunction "1_1") (pintype "passive"))
      (node (ref "R26") (pin "1") (pinfunction "1_1") (pintype "passive"))
      (node (ref "U17") (pin "7") (pinfunction "REXT/CEXT_7") (pintype "passive"))
    )
    (net (code "112") (name "Net-(U19A-Y)") (class "Default")
      (node (ref "Q11") (pin "2") (pinfunction "2_2") (pintype "passive"))
      (node (ref "U19") (pin "4") (pinfunction "Y_4") (pintype "output"))
    )
    (net (code "113") (name "Net-(U20-CEXT)") (class "Default")
      (node (ref "C67") (pin "2") (pinfunction "2_2") (pintype "passive"))
      (node (ref "U20") (pin "6") (pinfunction "CEXT_6") (pintype "passive"))
    )
    (net (code "114") (name "Net-(U20-REXT{slash}CEXT)") (class "Default")
      (node (ref "C67") (pin "1") (pinfunction "1_1") (pintype "passive"))
      (node (ref "R36") (pin "1") (pinfunction "1_1") (pintype "passive"))
      (node (ref "U20") (pin "7") (pinfunction "REXT/CEXT_7") (pintype "passive"))
    )
    (net (code "115") (name "VREF") (class "Default")
      (node (ref "C38") (pin "1") (pinfunction "1_1") (pintype "passive"))
      (node (ref "U8") (pin "10") (pinfunction "VREFIN/VREFOUT_10") (pintype "bidirectional"))
    )
    (net (code "116") (name "VREF{slash}2") (class "Default")
      (node (ref "U11") (pin "3") (pinfunction "IN+_3") (pintype "input"))
      (node (ref "U22") (pin "3") (pinfunction "IN+_3") (pintype "input"))
    )
    (net (code "117") (name "V_BUS") (class "Default")
      (node (ref "C58") (pin "1") (pinfunction "1_1") (pintype "passive"))
      (node (ref "D8") (pin "2") (pinfunction "2_2") (pintype "passive"))
      (node (ref "J5") (pin "1") (pinfunction "VBUS_1") (pintype "passive"))
      (node (ref "J6") (pin "3") (pinfunction "3_3") (pintype "passive"))
      (node (ref "U15") (pin "7") (pinfunction "REGIN_7") (pintype "power_in"))
      (node (ref "U15") (pin "8") (pinfunction "VBUS_8") (pintype "input"))
    )
    (net (code "118") (name "unconnected-(J7-MH-Pad6)") (class "Default")
      (node (ref "J7") (pin "6") (pinfunction "MH_6") (pintype "passive+no_connect"))
    )
    (net (code "119") (name "unconnected-(J8-Pad7)") (class "Default")
      (node (ref "J8") (pin "7") (pinfunction "7_7") (pintype "passive+no_connect"))
    )
    (net (code "120") (name "unconnected-(R19-Pad1)") (class "Default")
      (node (ref "R19") (pin "1") (pinfunction "1_1") (pintype "passive"))
    )
    (net (code "121") (name "unconnected-(R19-Pad4)") (class "Default")
      (node (ref "R19") (pin "4") (pinfunction "4_4") (pintype "passive"))
    )
    (net (code "122") (name "unconnected-(R19-Pad5)") (class "Default")
      (node (ref "R19") (pin "5") (pinfunction "5_5") (pintype "passive"))
    )
    (net (code "123") (name "unconnected-(R19-Pad6)") (class "Default")
      (node (ref "R19") (pin "6") (pinfunction "6_6") (pintype "passive"))
    )
    (net (code "124") (name "unconnected-(R19-Pad11)") (class "Default")
      (node (ref "R19") (pin "11") (pinfunction "11_11") (pintype "passive"))
    )
    (net (code "125") (name "unconnected-(R19-Pad12)") (class "Default")
      (node (ref "R19") (pin "12") (pinfunction "12_12") (pintype "passive"))
    )
    (net (code "126") (name "unconnected-(R19-Pad13)") (class "Default")
      (node (ref "R19") (pin "13") (pinfunction "13_13") (pintype "passive"))
    )
    (net (code "127") (name "unconnected-(R19-Pad16)") (class "Default")
      (node (ref "R19") (pin "16") (pinfunction "16_16") (pintype "passive"))
    )
    (net (code "128") (name "unconnected-(R23-Pad8)") (class "Default")
      (node (ref "R23") (pin "8") (pinfunction "8_8") (pintype "passive"))
    )
    (net (code "129") (name "unconnected-(R23-Pad9)") (class "Default")
      (node (ref "R23") (pin "9") (pinfunction "9_9") (pintype "passive"))
    )
    (net (code "130") (name "unconnected-(R24-Pad7)") (class "Default")
      (node (ref "R24") (pin "7") (pinfunction "7_7") (pintype "passive"))
    )
    (net (code "131") (name "unconnected-(R24-Pad8)") (class "Default")
      (node (ref "R24") (pin "8") (pinfunction "8_8") (pintype "passive"))
    )
    (net (code "132") (name "unconnected-(R24-Pad9)") (class "Default")
      (node (ref "R24") (pin "9") (pinfunction "9_9") (pintype "passive"))
    )
    (net (code "133") (name "unconnected-(R24-Pad10)") (class "Default")
      (node (ref "R24") (pin "10") (pinfunction "10_10") (pintype "passive"))
    )
    (net (code "134") (name "unconnected-(R31-Pad1)") (class "Default")
      (node (ref "R31") (pin "1") (pinfunction "1_1") (pintype "passive"))
    )
    (net (code "135") (name "unconnected-(R31-Pad16)") (class "Default")
      (node (ref "R31") (pin "16") (pinfunction "16_16") (pintype "passive"))
    )
    (net (code "136") (name "unconnected-(U10-S1-Pad2)") (class "Default")
      (node (ref "U10") (pin "2") (pinfunction "S1_2") (pintype "passive"))
    )
    (net (code "137") (name "unconnected-(U11-~{SHDN}-Pad5)") (class "Default")
      (node (ref "U11") (pin "5") (pinfunction "~{SHDN}_5") (pintype "input+no_connect"))
    )
    (net (code "138") (name "unconnected-(U13B-NC-Pad1)") (class "Default")
      (node (ref "U13") (pin "1") (pinfunction "NC_1") (pintype "passive"))
    )
    (net (code "139") (name "unconnected-(U15-GPIO.0-Pad14)") (class "Default")
      (node (ref "U15") (pin "14") (pinfunction "GPIO.0_14") (pintype "bidirectional+no_connect"))
    )
    (net (code "140") (name "unconnected-(U15-GPIO.1-Pad13)") (class "Default")
      (node (ref "U15") (pin "13") (pinfunction "GPIO.1_13") (pintype "bidirectional+no_connect"))
    )
    (net (code "141") (name "unconnected-(U15-GPIO.2-Pad12)") (class "Default")
      (node (ref "U15") (pin "12") (pinfunction "GPIO.2_12") (pintype "bidirectional+no_connect"))
    )
    (net (code "142") (name "unconnected-(U15-GPIO.3-Pad11)") (class "Default")
      (node (ref "U15") (pin "11") (pinfunction "GPIO.3_11") (pintype "bidirectional+no_connect"))
    )
    (net (code "143") (name "unconnected-(U15-NC-Pad10)") (class "Default")
      (node (ref "U15") (pin "10") (pinfunction "NC_10") (pintype "passive"))
    )
    (net (code "144") (name "unconnected-(U15-SUSPEND-Pad17)") (class "Default")
      (node (ref "U15") (pin "17") (pinfunction "SUSPEND_17") (pintype "output+no_connect"))
    )
    (net (code "145") (name "unconnected-(U15-~{CTS}-Pad18)") (class "Default")
      (node (ref "U15") (pin "18") (pinfunction "~{CTS}_18") (pintype "input+no_connect"))
    )
    (net (code "146") (name "unconnected-(U15-~{DCD}-Pad24)") (class "Default")
      (node (ref "U15") (pin "24") (pinfunction "~{DCD}_24") (pintype "input+no_connect"))
    )
    (net (code "147") (name "unconnected-(U15-~{DSR}-Pad22)") (class "Default")
      (node (ref "U15") (pin "22") (pinfunction "~{DSR}_22") (pintype "input+no_connect"))
    )
    (net (code "148") (name "unconnected-(U15-~{DTR}-Pad23)") (class "Default")
      (node (ref "U15") (pin "23") (pinfunction "~{DTR}_23") (pintype "output+no_connect"))
    )
    (net (code "149") (name "unconnected-(U15-~{RI}-Pad1)") (class "Default")
      (node (ref "U15") (pin "1") (pinfunction "~{RI}_1") (pintype "input+no_connect"))
    )
    (net (code "150") (name "unconnected-(U15-~{RTS}-Pad19)") (class "Default")
      (node (ref "U15") (pin "19") (pinfunction "~{RTS}_19") (pintype "output+no_connect"))
    )
    (net (code "151") (name "unconnected-(U15-~{SUSPEND}-Pad15)") (class "Default")
      (node (ref "U15") (pin "15") (pinfunction "~{SUSPEND}_15") (pintype "output+no_connect"))
    )
    (net (code "152") (name "unconnected-(U19B-NC-Pad1)") (class "Default")
      (node (ref "U19") (pin "1") (pinfunction "NC_1") (pintype "passive"))
    )
    (net (code "153") (name "unconnected-(U22-~{SHDN}-Pad5)") (class "Default")
      (node (ref "U22") (pin "5") (pinfunction "~{SHDN}_5") (pintype "input+no_connect"))
    )
  )
)
